# Tarjeta_Prototipo_L6470.net
KiCad netlist of a schematic drawn in EAGLE
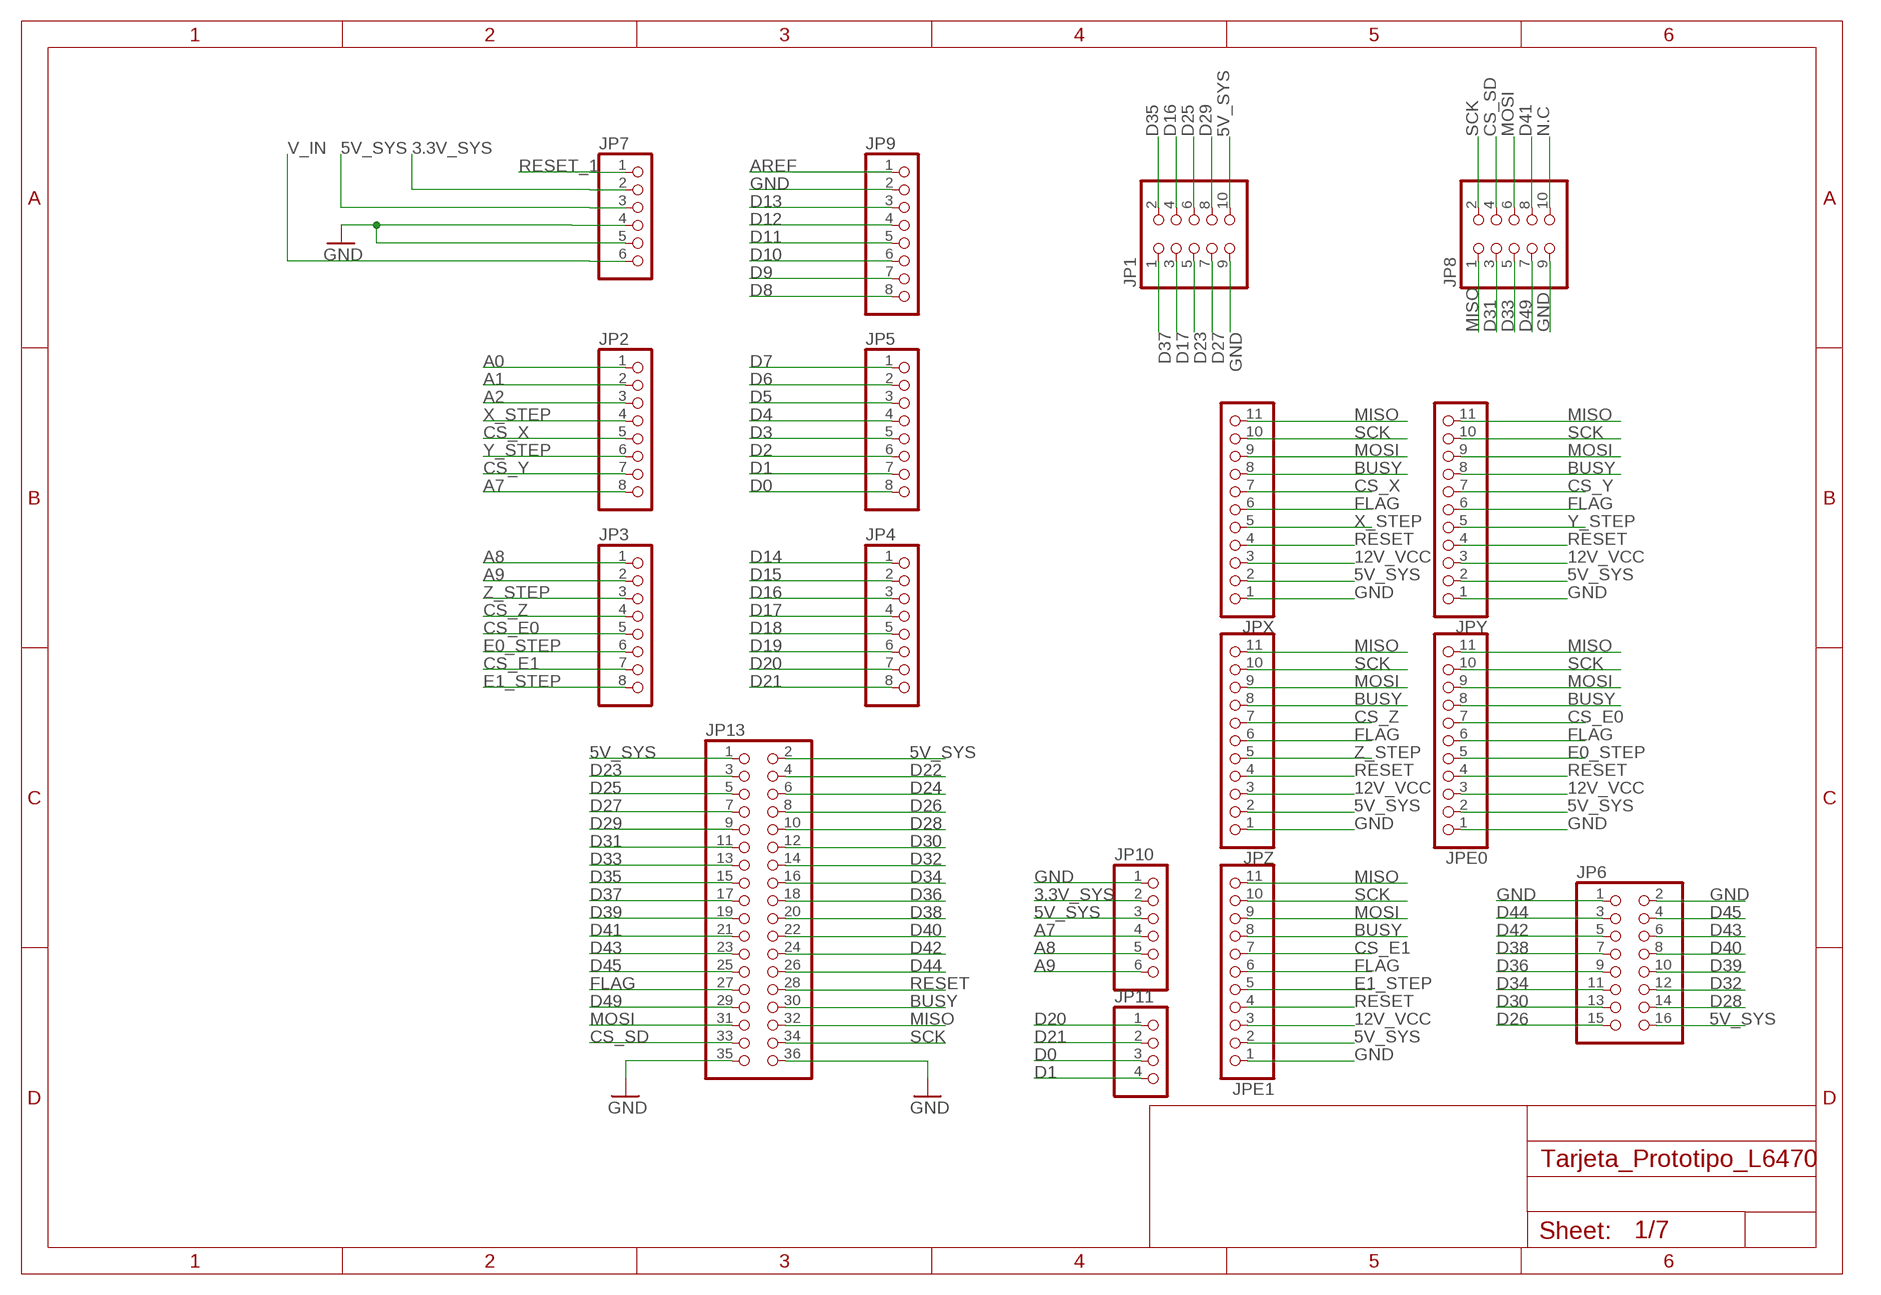
[diagram p0: schematic, sheet 1]
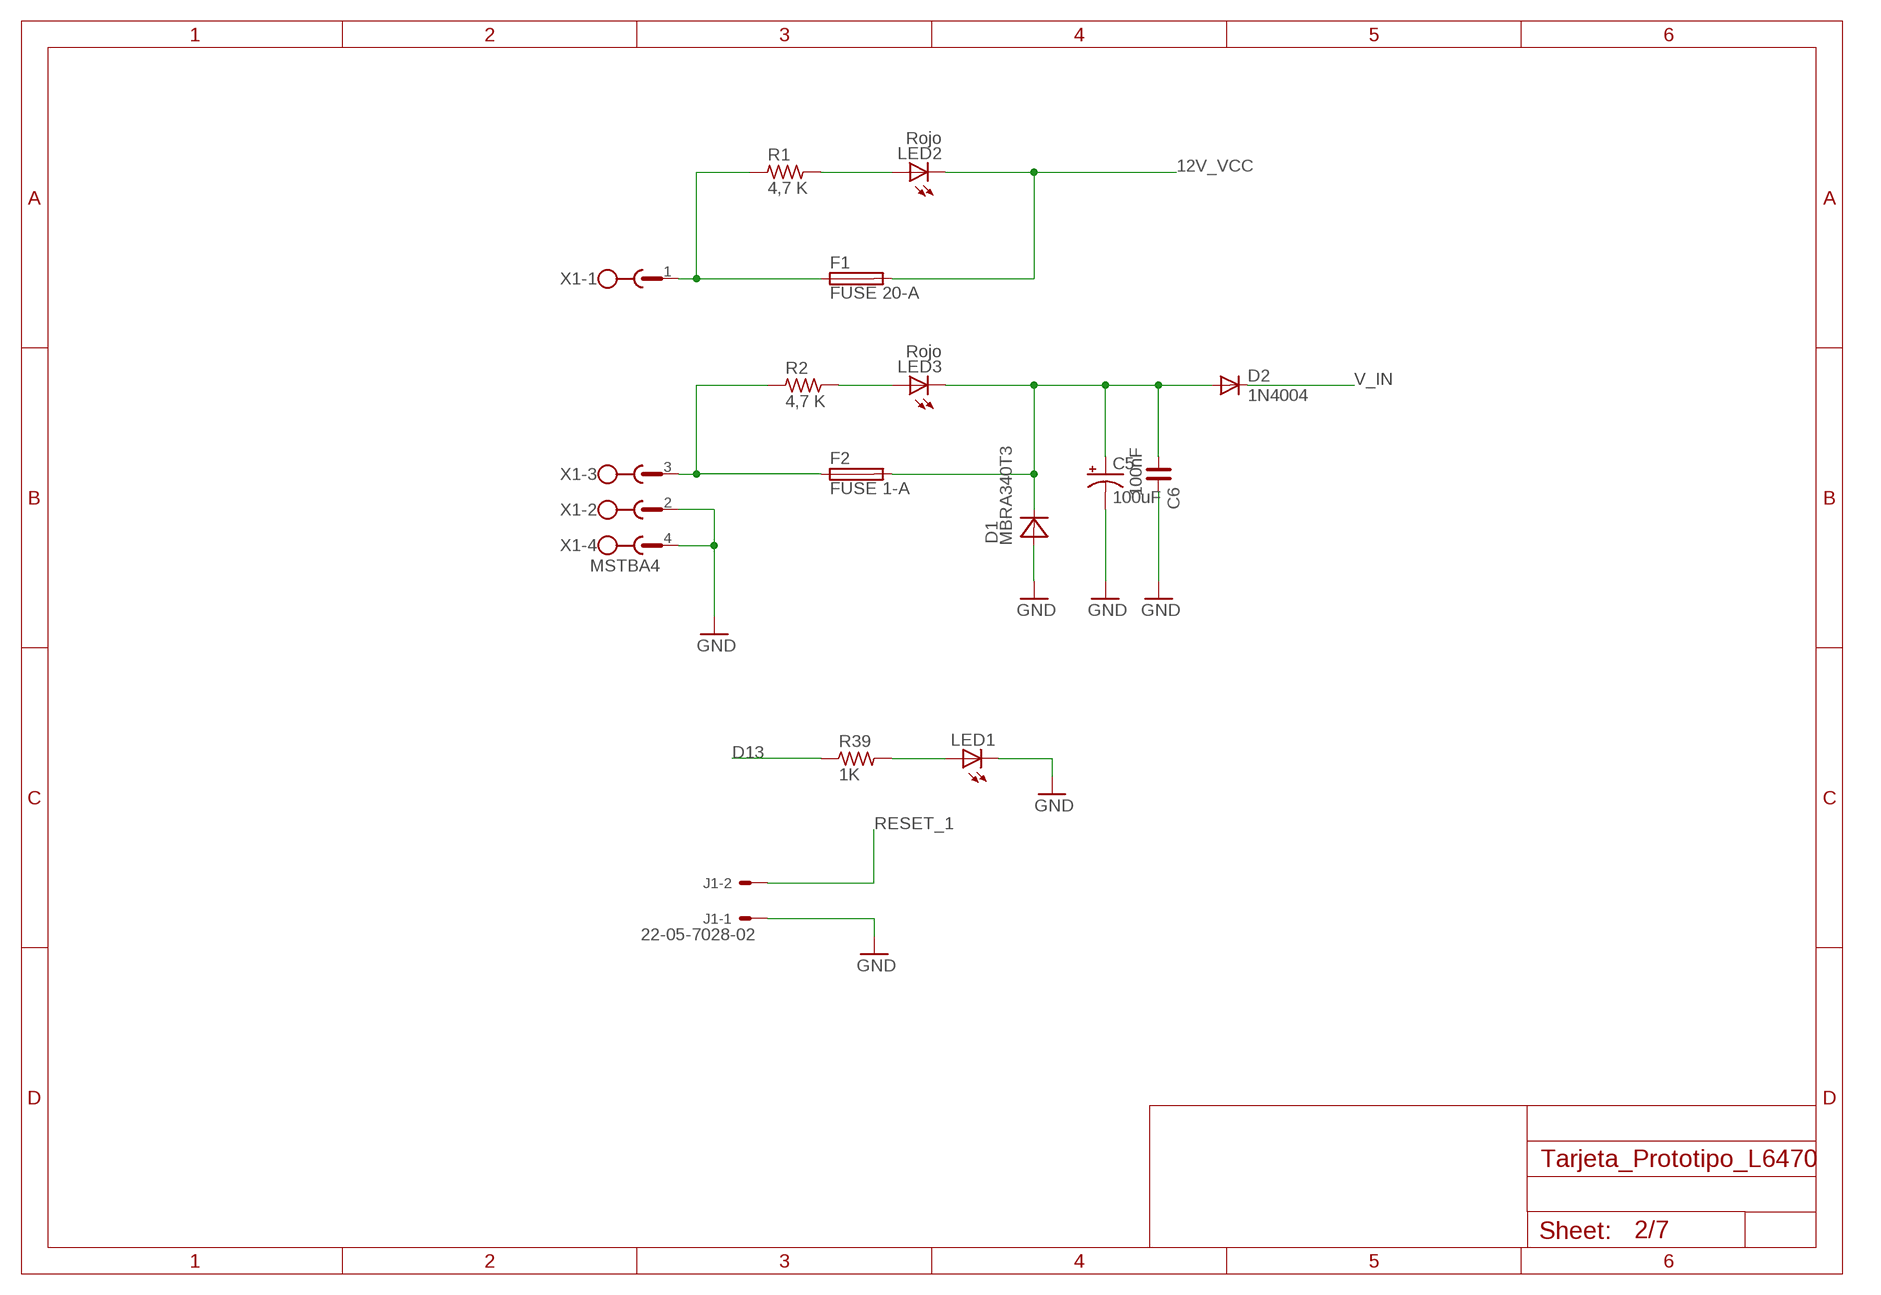
[diagram p1: schematic, sheet 2]
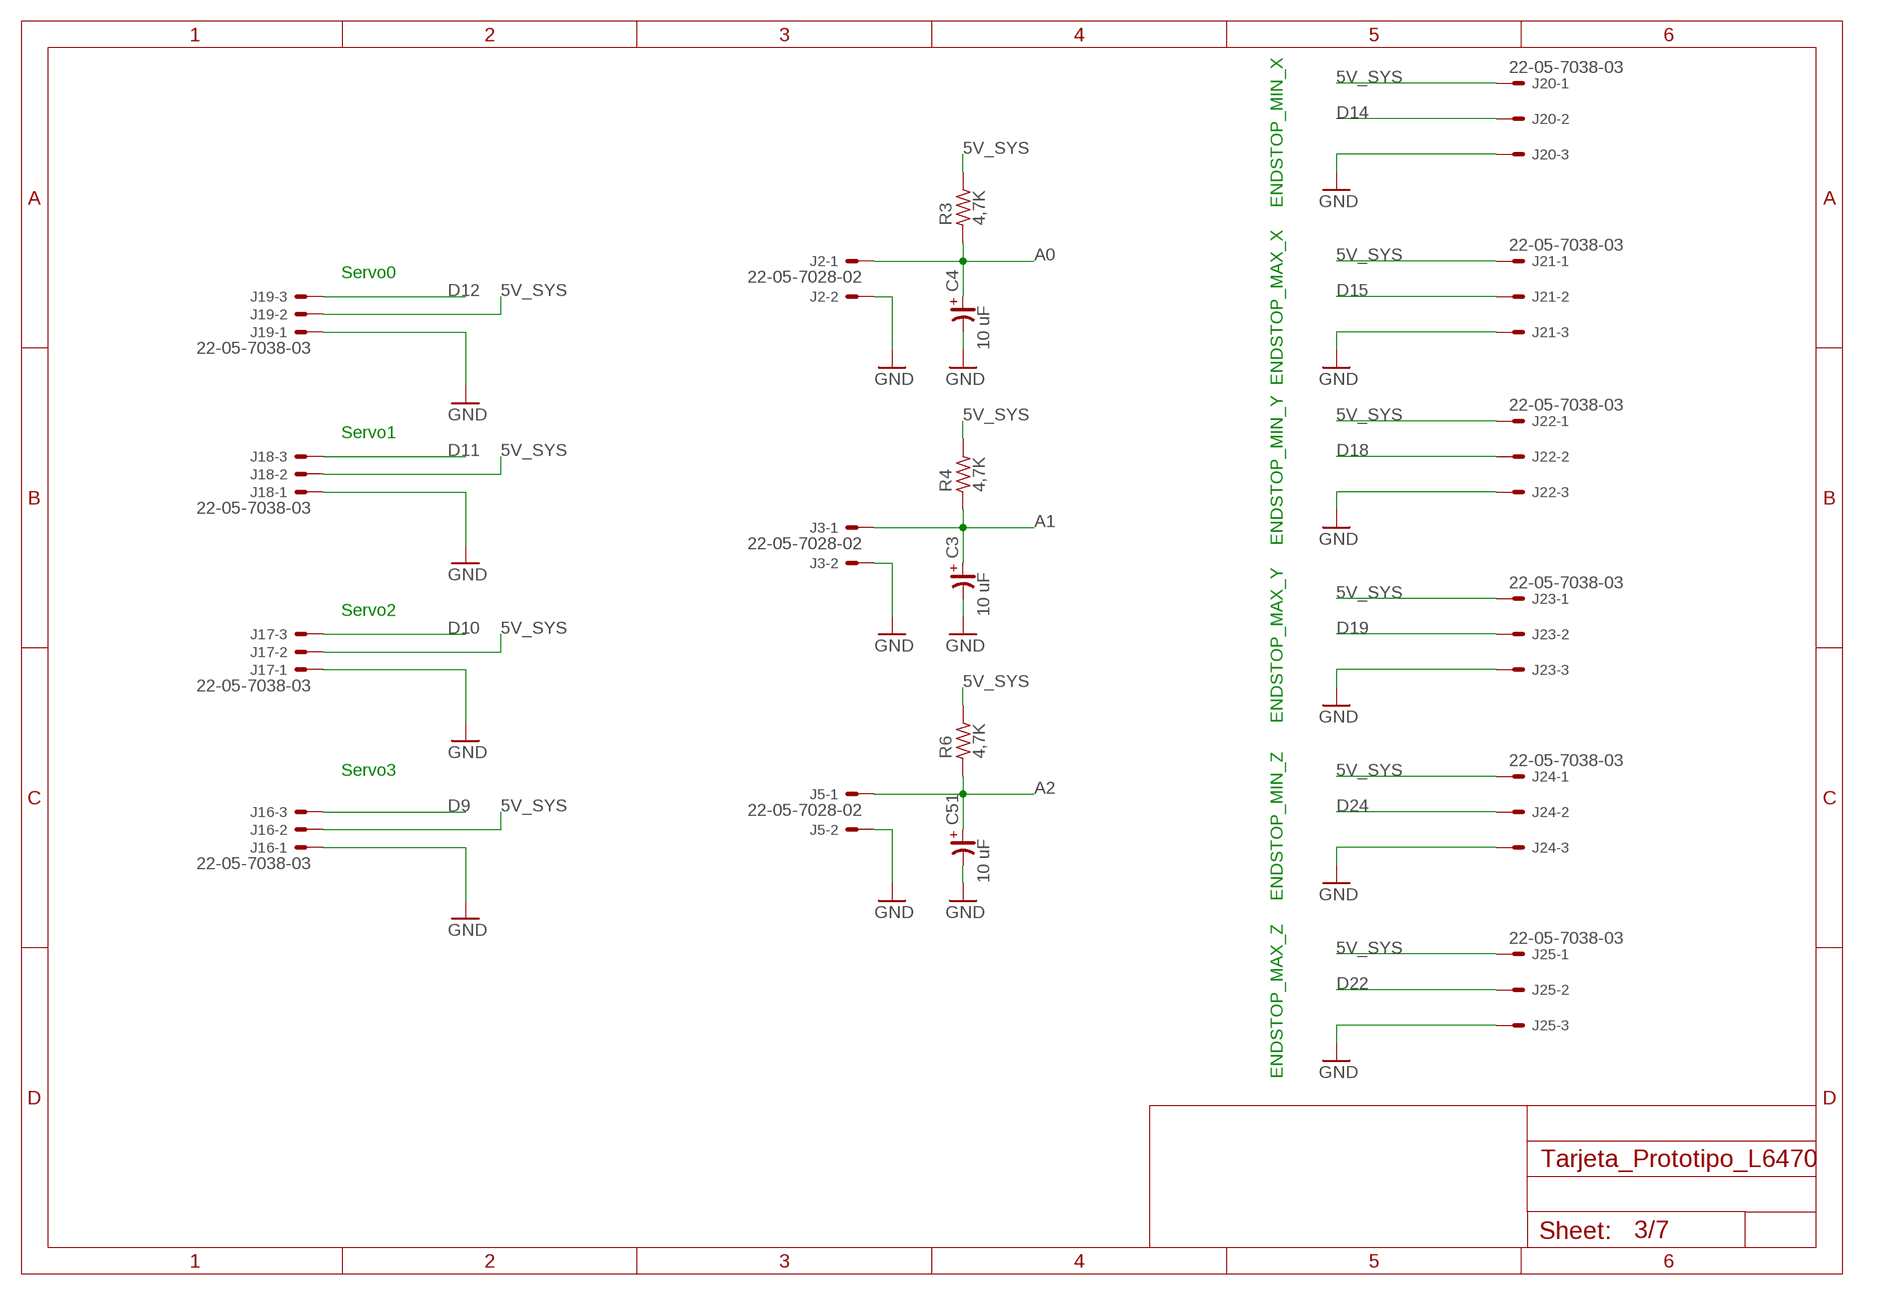
[diagram p2: schematic, sheet 3]
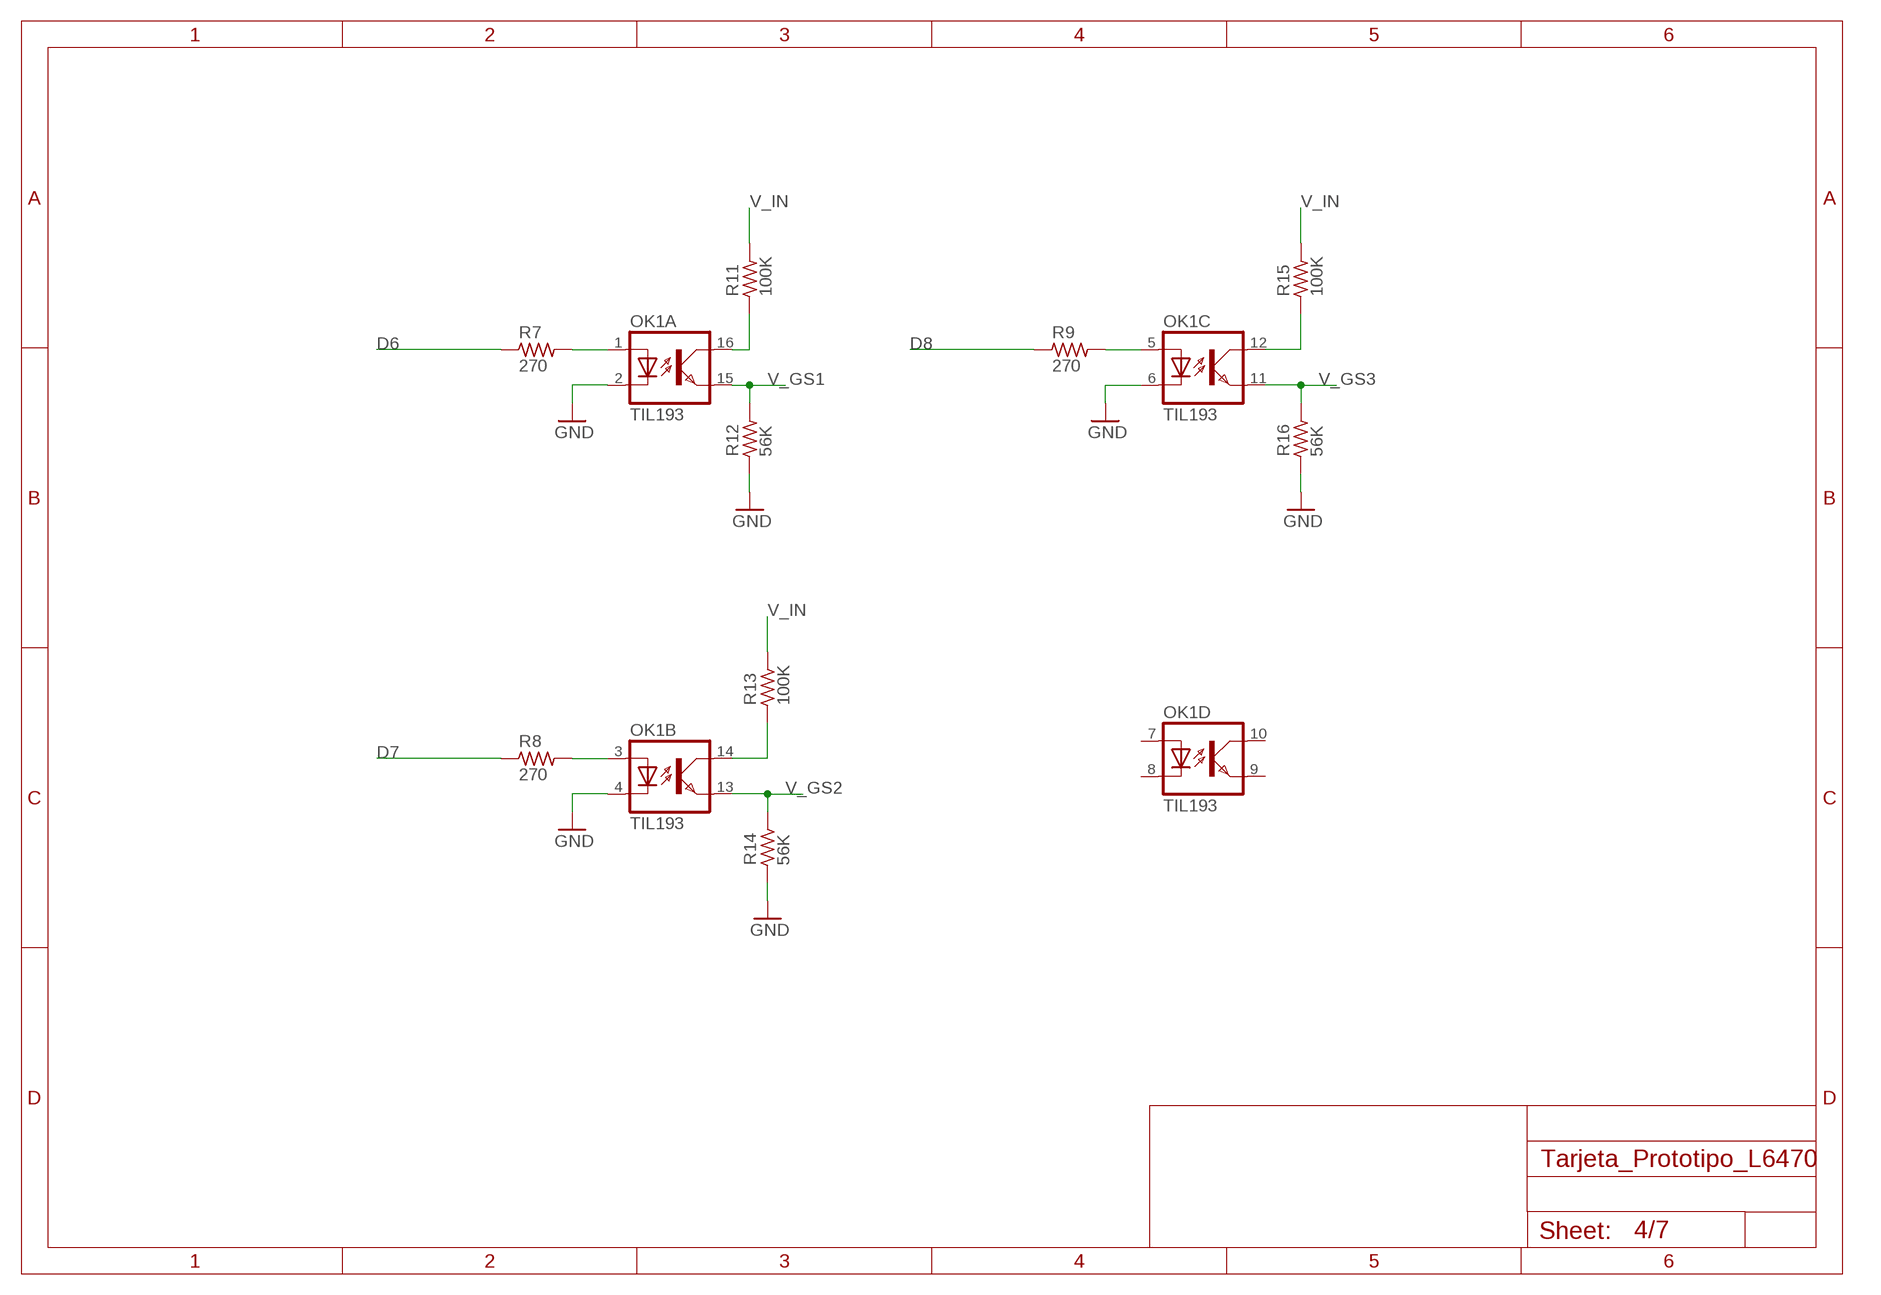
[diagram p3: schematic, sheet 4]
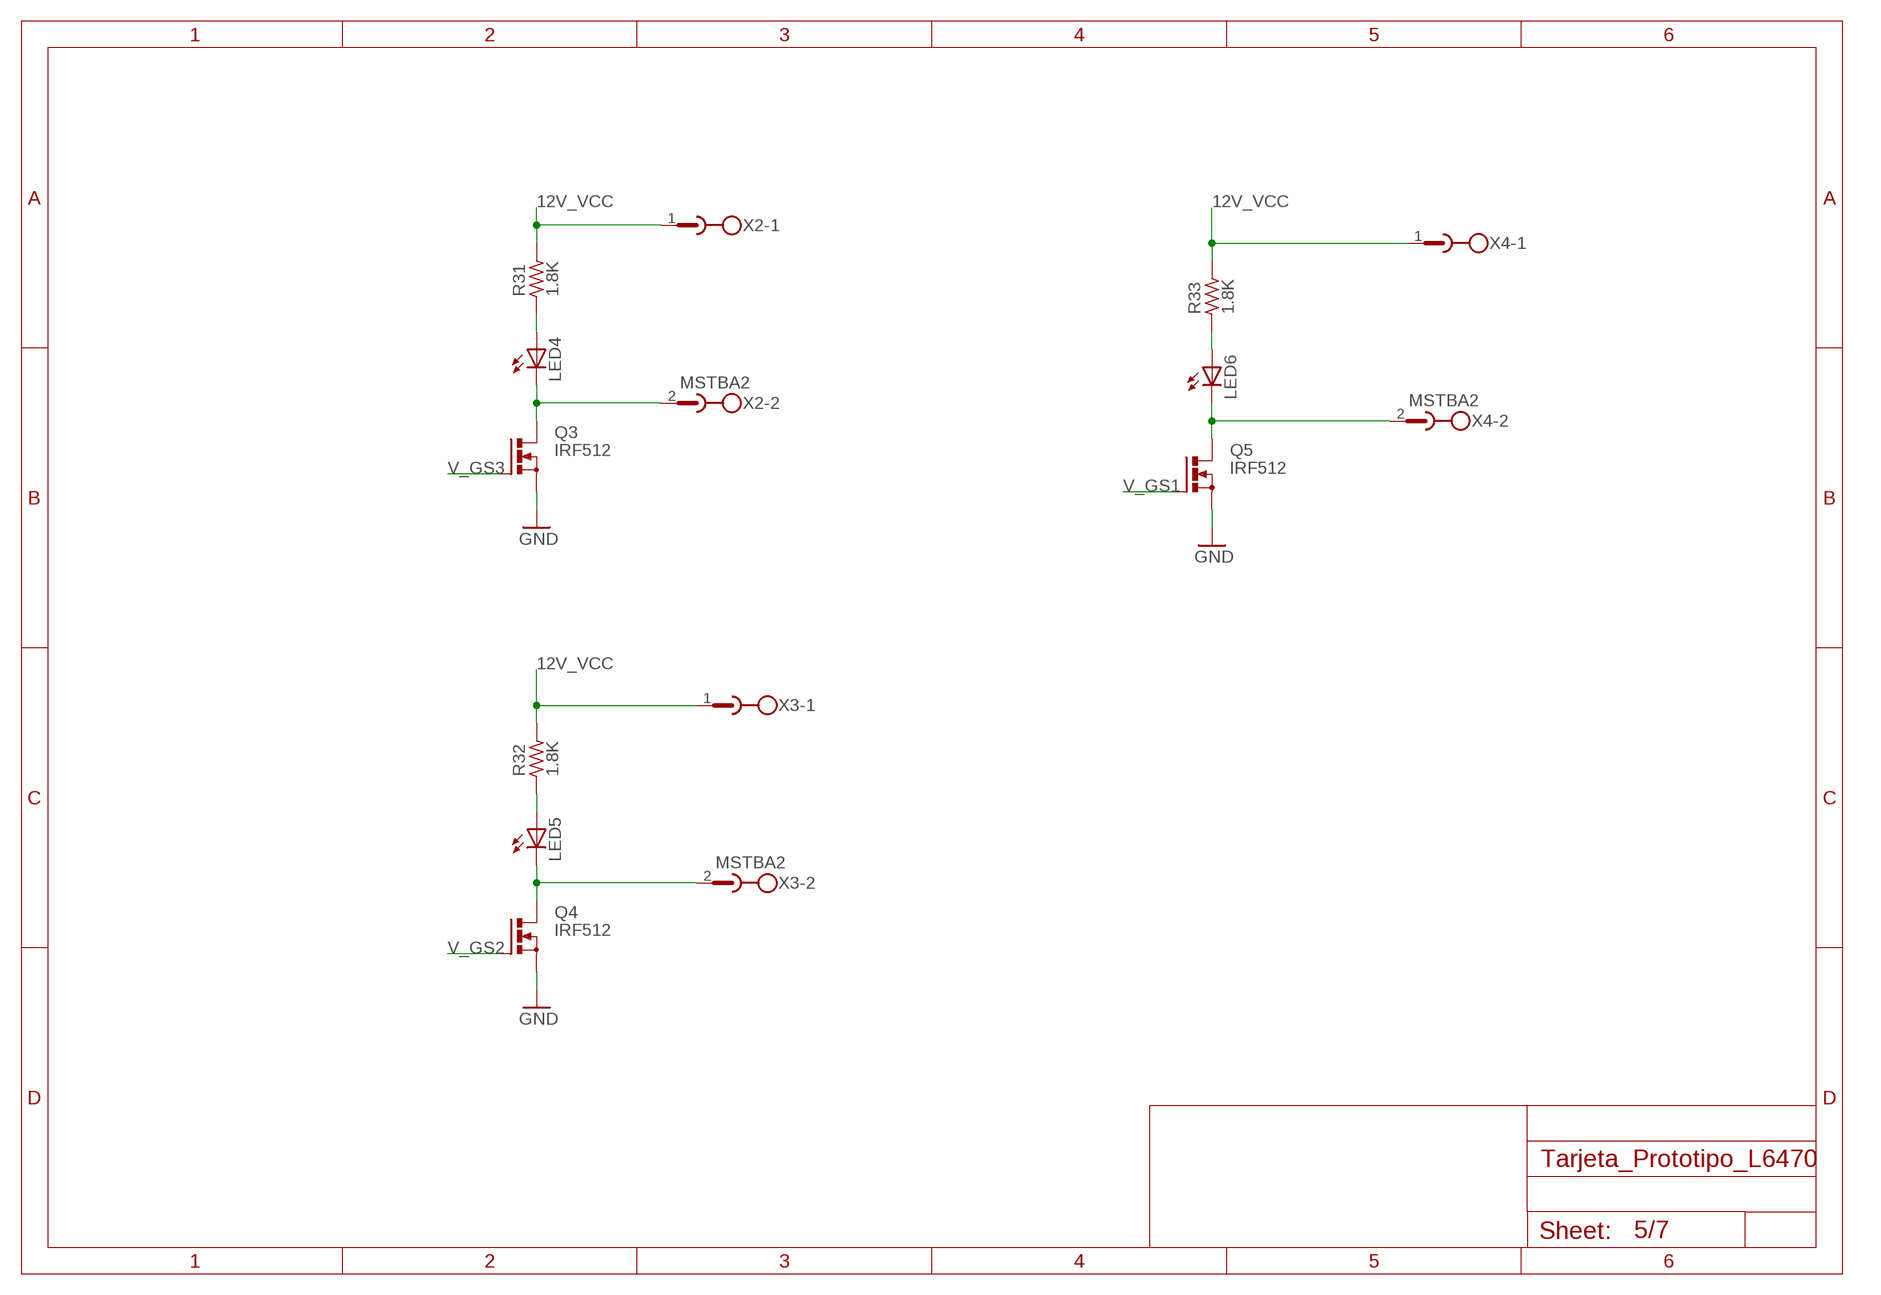
[diagram p4: schematic, sheet 5]
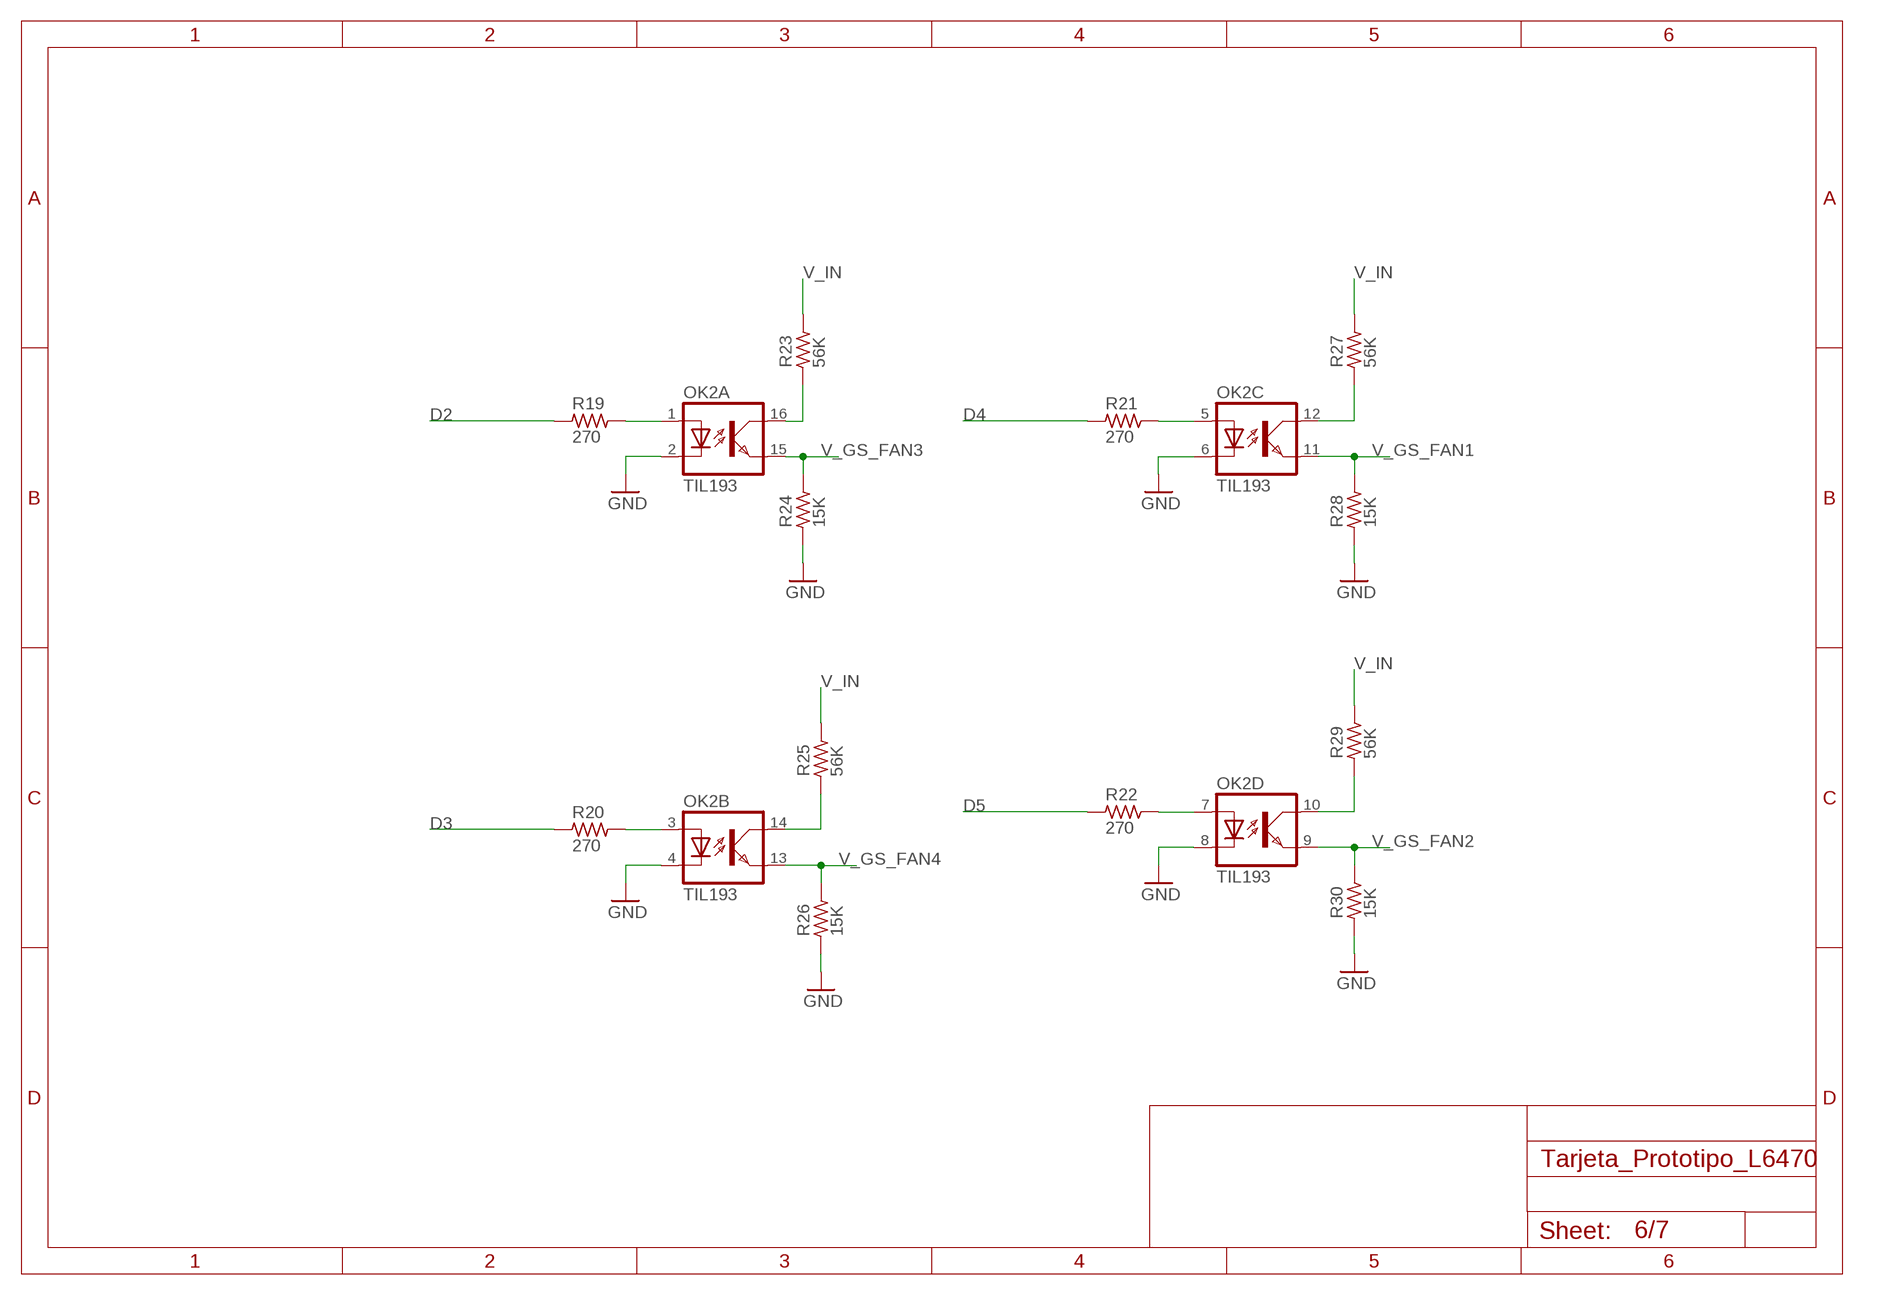
[diagram p5: schematic, sheet 6]
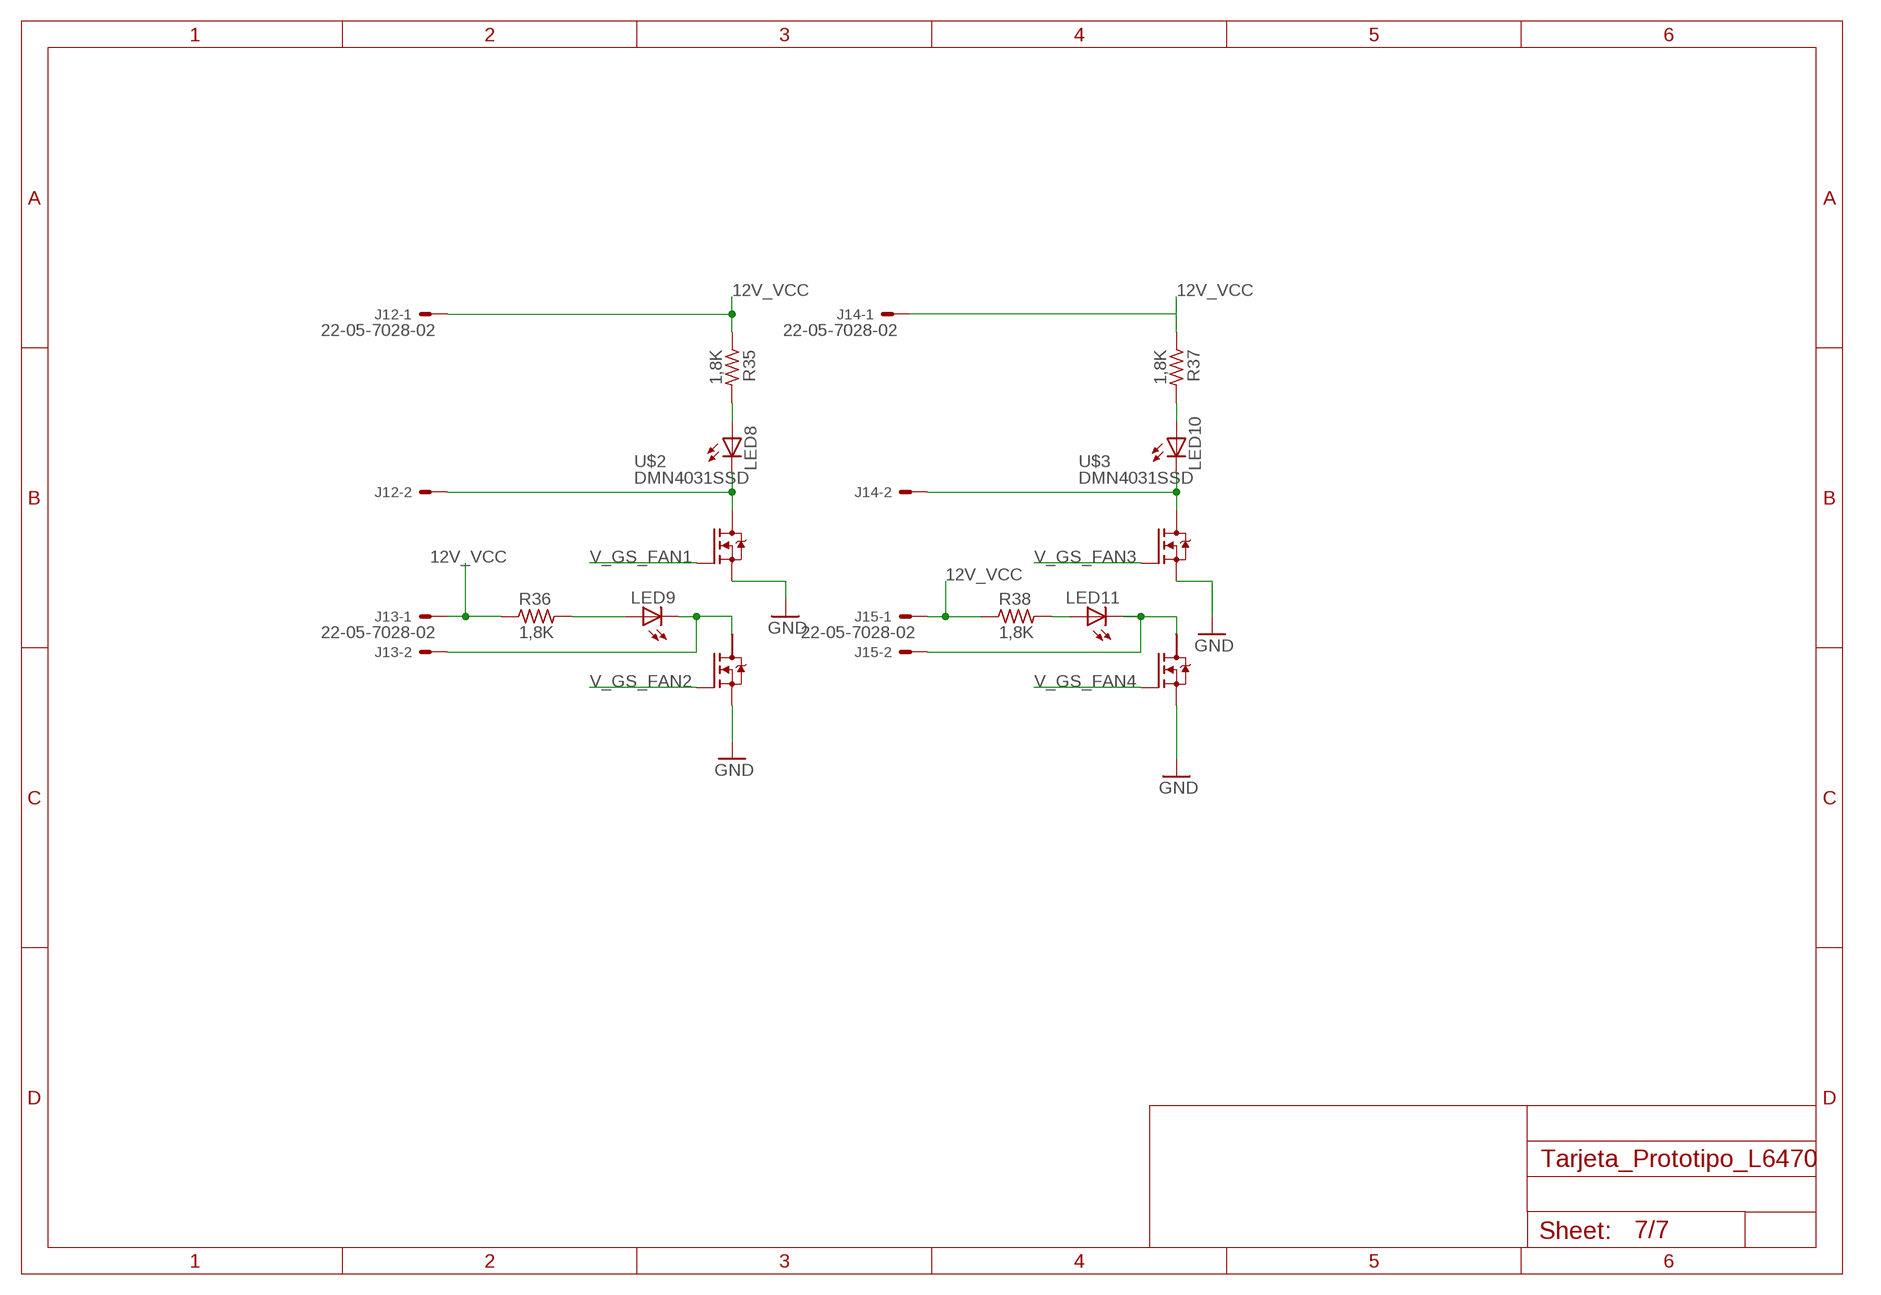
[diagram p6: schematic, sheet 7]

(export (version "E")
  (design (tool "Eeschema 10.0.6"))
  (components
    (comp (ref "OK1")
      (value "TIL193")
      (footprint "eagle-import:DIL16")
      (libsource (lib "eagle-import") (part "TIL193"))
    )
    (comp (ref "R7")
      (value "270")
      (footprint "eagle-import:R1206")
      (libsource (lib "eagle-import") (part "R_1206"))
    )
    (comp (ref "R8")
      (value "270")
      (footprint "eagle-import:R1206")
      (libsource (lib "eagle-import") (part "R_1206"))
    )
    (comp (ref "R9")
      (value "270")
      (footprint "eagle-import:R1206")
      (libsource (lib "eagle-import") (part "R_1206"))
    )
    (comp (ref "R11")
      (value "100K")
      (footprint "eagle-import:R1206")
      (libsource (lib "eagle-import") (part "R_1206"))
    )
    (comp (ref "R12")
      (value "56K")
      (footprint "eagle-import:R1206")
      (libsource (lib "eagle-import") (part "R_1206"))
    )
    (comp (ref "R13")
      (value "100K")
      (footprint "eagle-import:R1206")
      (libsource (lib "eagle-import") (part "R_1206"))
    )
    (comp (ref "R14")
      (value "56K")
      (footprint "eagle-import:R1206")
      (libsource (lib "eagle-import") (part "R_1206"))
    )
    (comp (ref "R15")
      (value "100K")
      (footprint "eagle-import:R1206")
      (libsource (lib "eagle-import") (part "R_1206"))
    )
    (comp (ref "R16")
      (value "56K")
      (footprint "eagle-import:R1206")
      (libsource (lib "eagle-import") (part "R_1206"))
    )
    (comp (ref "C3")
      (value "10 uF")
      (footprint "eagle-import:CSV-B")
      (libsource (lib "eagle-import") (part "CP_SV-B"))
    )
    (comp (ref "C4")
      (value "10 uF")
      (footprint "eagle-import:CSV-B")
      (libsource (lib "eagle-import") (part "CP_SV-B"))
    )
    (comp (ref "C51")
      (value "10 uF")
      (footprint "eagle-import:CSV-B")
      (libsource (lib "eagle-import") (part "CP_SV-B"))
    )
    (comp (ref "J2")
      (value "22-05-7028-02")
      (footprint "eagle-import:7395-02")
      (libsource (lib "eagle-import") (part "22-?-0205-7028"))
    )
    (comp (ref "J3")
      (value "22-05-7028-02")
      (footprint "eagle-import:7395-02")
      (libsource (lib "eagle-import") (part "22-?-0205-7028"))
    )
    (comp (ref "J5")
      (value "22-05-7028-02")
      (footprint "eagle-import:7395-02")
      (libsource (lib "eagle-import") (part "22-?-0205-7028"))
    )
    (comp (ref "J16")
      (value "22-05-7038-03")
      (footprint "eagle-import:7395-03")
      (libsource (lib "eagle-import") (part "22-?-0305-7038"))
    )
    (comp (ref "J17")
      (value "22-05-7038-03")
      (footprint "eagle-import:7395-03")
      (libsource (lib "eagle-import") (part "22-?-0305-7038"))
    )
    (comp (ref "J18")
      (value "22-05-7038-03")
      (footprint "eagle-import:7395-03")
      (libsource (lib "eagle-import") (part "22-?-0305-7038"))
    )
    (comp (ref "J19")
      (value "22-05-7038-03")
      (footprint "eagle-import:7395-03")
      (libsource (lib "eagle-import") (part "22-?-0305-7038"))
    )
    (comp (ref "J20")
      (value "22-05-7038-03")
      (footprint "eagle-import:7395-03")
      (libsource (lib "eagle-import") (part "22-?-0305-7038"))
    )
    (comp (ref "J21")
      (value "22-05-7038-03")
      (footprint "eagle-import:7395-03")
      (libsource (lib "eagle-import") (part "22-?-0305-7038"))
    )
    (comp (ref "J22")
      (value "22-05-7038-03")
      (footprint "eagle-import:7395-03")
      (libsource (lib "eagle-import") (part "22-?-0305-7038"))
    )
    (comp (ref "J23")
      (value "22-05-7038-03")
      (footprint "eagle-import:7395-03")
      (libsource (lib "eagle-import") (part "22-?-0305-7038"))
    )
    (comp (ref "J24")
      (value "22-05-7038-03")
      (footprint "eagle-import:7395-03")
      (libsource (lib "eagle-import") (part "22-?-0305-7038"))
    )
    (comp (ref "J25")
      (value "22-05-7038-03")
      (footprint "eagle-import:7395-03")
      (libsource (lib "eagle-import") (part "22-?-0305-7038"))
    )
    (comp (ref "R3")
      (value "4,7K")
      (footprint "eagle-import:R1206")
      (libsource (lib "eagle-import") (part "R_1206"))
    )
    (comp (ref "R4")
      (value "4,7K")
      (footprint "eagle-import:R1206")
      (libsource (lib "eagle-import") (part "R_1206"))
    )
    (comp (ref "R6")
      (value "4,7K")
      (footprint "eagle-import:R1206")
      (libsource (lib "eagle-import") (part "R_1206"))
    )
    (comp (ref "OK2")
      (value "TIL193")
      (footprint "eagle-import:DIL16")
      (libsource (lib "eagle-import") (part "TIL193"))
    )
    (comp (ref "R19")
      (value "270")
      (footprint "eagle-import:R1206")
      (libsource (lib "eagle-import") (part "R_1206"))
    )
    (comp (ref "R20")
      (value "270")
      (footprint "eagle-import:R1206")
      (libsource (lib "eagle-import") (part "R_1206"))
    )
    (comp (ref "R21")
      (value "270")
      (footprint "eagle-import:R1206")
      (libsource (lib "eagle-import") (part "R_1206"))
    )
    (comp (ref "R22")
      (value "270")
      (footprint "eagle-import:R1206")
      (libsource (lib "eagle-import") (part "R_1206"))
    )
    (comp (ref "R23")
      (value "56K")
      (footprint "eagle-import:R1206")
      (libsource (lib "eagle-import") (part "R_1206"))
    )
    (comp (ref "R24")
      (value "15K")
      (footprint "eagle-import:R1206")
      (libsource (lib "eagle-import") (part "R_1206"))
    )
    (comp (ref "R25")
      (value "56K")
      (footprint "eagle-import:R1206")
      (libsource (lib "eagle-import") (part "R_1206"))
    )
    (comp (ref "R26")
      (value "15K")
      (footprint "eagle-import:R1206")
      (libsource (lib "eagle-import") (part "R_1206"))
    )
    (comp (ref "R27")
      (value "56K")
      (footprint "eagle-import:R1206")
      (libsource (lib "eagle-import") (part "R_1206"))
    )
    (comp (ref "R28")
      (value "15K")
      (footprint "eagle-import:R1206")
      (libsource (lib "eagle-import") (part "R_1206"))
    )
    (comp (ref "R29")
      (value "56K")
      (footprint "eagle-import:R1206")
      (libsource (lib "eagle-import") (part "R_1206"))
    )
    (comp (ref "R30")
      (value "15K")
      (footprint "eagle-import:R1206")
      (libsource (lib "eagle-import") (part "R_1206"))
    )
    (comp (ref "JP1")
      (value "PINHD-2X5")
      (footprint "eagle-import:2X05")
      (libsource (lib "eagle-import") (part "PINHD-2X5"))
    )
    (comp (ref "JP2")
      (value "PINHD-1X8")
      (footprint "eagle-import:1X08")
      (libsource (lib "eagle-import") (part "PINHD-1X8"))
    )
    (comp (ref "JP3")
      (value "PINHD-1X8")
      (footprint "eagle-import:1X08")
      (libsource (lib "eagle-import") (part "PINHD-1X8"))
    )
    (comp (ref "JP4")
      (value "PINHD-1X8")
      (footprint "eagle-import:1X08")
      (libsource (lib "eagle-import") (part "PINHD-1X8"))
    )
    (comp (ref "JP5")
      (value "PINHD-1X8")
      (footprint "eagle-import:1X08")
      (libsource (lib "eagle-import") (part "PINHD-1X8"))
    )
    (comp (ref "JP6")
      (value "PINHD-2X8")
      (footprint "eagle-import:2X08")
      (libsource (lib "eagle-import") (part "PINHD-2X8"))
    )
    (comp (ref "JP7")
      (value "PINHD-1X6")
      (footprint "eagle-import:1X06")
      (libsource (lib "eagle-import") (part "PINHD-1X6"))
    )
    (comp (ref "JP8")
      (value "PINHD-2X5")
      (footprint "eagle-import:2X05")
      (libsource (lib "eagle-import") (part "PINHD-2X5"))
    )
    (comp (ref "JP9")
      (value "PINHD-1X8")
      (footprint "eagle-import:1X08")
      (libsource (lib "eagle-import") (part "PINHD-1X8"))
    )
    (comp (ref "JP10")
      (value "PINHD-1X6")
      (footprint "eagle-import:1X06")
      (libsource (lib "eagle-import") (part "PINHD-1X6"))
    )
    (comp (ref "JP11")
      (value "PINHD-1X4")
      (footprint "eagle-import:1X04")
      (libsource (lib "eagle-import") (part "PINHD-1X4"))
    )
    (comp (ref "JP13")
      (value "PINHD-2X18")
      (footprint "eagle-import:2X18")
      (libsource (lib "eagle-import") (part "PINHD-2X18"))
    )
    (comp (ref "JPE0")
      (value "PINHD-1X11")
      (footprint "eagle-import:1X11")
      (libsource (lib "eagle-import") (part "PINHD-1X11"))
    )
    (comp (ref "JPE1")
      (value "PINHD-1X11")
      (footprint "eagle-import:1X11")
      (libsource (lib "eagle-import") (part "PINHD-1X11"))
    )
    (comp (ref "JPX")
      (value "PINHD-1X11")
      (footprint "eagle-import:1X11")
      (libsource (lib "eagle-import") (part "PINHD-1X11"))
    )
    (comp (ref "JPY")
      (value "PINHD-1X11")
      (footprint "eagle-import:1X11")
      (libsource (lib "eagle-import") (part "PINHD-1X11"))
    )
    (comp (ref "JPZ")
      (value "PINHD-1X11")
      (footprint "eagle-import:1X11")
      (libsource (lib "eagle-import") (part "PINHD-1X11"))
    )
    (comp (ref "J12")
      (value "22-05-7028-02")
      (footprint "eagle-import:7395-02")
      (libsource (lib "eagle-import") (part "22-?-0205-7028"))
    )
    (comp (ref "J13")
      (value "22-05-7028-02")
      (footprint "eagle-import:7395-02")
      (libsource (lib "eagle-import") (part "22-?-0205-7028"))
    )
    (comp (ref "J14")
      (value "22-05-7028-02")
      (footprint "eagle-import:7395-02")
      (libsource (lib "eagle-import") (part "22-?-0205-7028"))
    )
    (comp (ref "J15")
      (value "22-05-7028-02")
      (footprint "eagle-import:7395-02")
      (libsource (lib "eagle-import") (part "22-?-0205-7028"))
    )
    (comp (ref "LED8")
      (value "LEDSMT1206")
      (footprint "eagle-import:1206")
      (libsource (lib "eagle-import") (part "LEDSMT1206"))
    )
    (comp (ref "LED9")
      (value "LEDSMT1206")
      (footprint "eagle-import:1206")
      (libsource (lib "eagle-import") (part "LEDSMT1206"))
    )
    (comp (ref "LED10")
      (value "LEDSMT1206")
      (footprint "eagle-import:1206")
      (libsource (lib "eagle-import") (part "LEDSMT1206"))
    )
    (comp (ref "LED11")
      (value "LEDSMT1206")
      (footprint "eagle-import:1206")
      (libsource (lib "eagle-import") (part "LEDSMT1206"))
    )
    (comp (ref "R35")
      (value "1,8K")
      (footprint "eagle-import:R1206")
      (libsource (lib "eagle-import") (part "R_1206"))
    )
    (comp (ref "R36")
      (value "1,8K")
      (footprint "eagle-import:R1206")
      (libsource (lib "eagle-import") (part "R_1206"))
    )
    (comp (ref "R37")
      (value "1,8K")
      (footprint "eagle-import:R1206")
      (libsource (lib "eagle-import") (part "R_1206"))
    )
    (comp (ref "R38")
      (value "1,8K")
      (footprint "eagle-import:R1206")
      (libsource (lib "eagle-import") (part "R_1206"))
    )
    (comp (ref "U$2")
      (value "DMN4031SSD")
      (footprint "eagle-import:DMN4031SSD")
      (libsource (lib "eagle-import") (part "DMN4031SSD"))
    )
    (comp (ref "U$3")
      (value "DMN4031SSD")
      (footprint "eagle-import:DMN4031SSD")
      (libsource (lib "eagle-import") (part "DMN4031SSD"))
    )
    (comp (ref "LED4")
      (value "LEDSMT1206")
      (footprint "eagle-import:1206")
      (libsource (lib "eagle-import") (part "LEDSMT1206"))
    )
    (comp (ref "LED5")
      (value "LEDSMT1206")
      (footprint "eagle-import:1206")
      (libsource (lib "eagle-import") (part "LEDSMT1206"))
    )
    (comp (ref "LED6")
      (value "LEDSMT1206")
      (footprint "eagle-import:1206")
      (libsource (lib "eagle-import") (part "LEDSMT1206"))
    )
    (comp (ref "Q3")
      (value "IRF512")
      (footprint "eagle-import:TO220BV")
      (libsource (lib "eagle-import") (part "IRF512"))
    )
    (comp (ref "Q4")
      (value "IRF512")
      (footprint "eagle-import:TO220BV")
      (libsource (lib "eagle-import") (part "IRF512"))
    )
    (comp (ref "Q5")
      (value "IRF512")
      (footprint "eagle-import:TO220BV")
      (libsource (lib "eagle-import") (part "IRF512"))
    )
    (comp (ref "R31")
      (value "1.8K")
      (footprint "eagle-import:R1206")
      (libsource (lib "eagle-import") (part "R_1206"))
    )
    (comp (ref "R32")
      (value "1.8K")
      (footprint "eagle-import:R1206")
      (libsource (lib "eagle-import") (part "R_1206"))
    )
    (comp (ref "R33")
      (value "1.8K")
      (footprint "eagle-import:R1206")
      (libsource (lib "eagle-import") (part "R_1206"))
    )
    (comp (ref "X2")
      (value "MSTBA2")
      (footprint "eagle-import:MSTBA2")
      (fields (field (name "MF") "FARNELL") (field (name "MPN") "1757242"))
      (libsource (lib "eagle-import") (part "MSTBA2"))
    )
    (comp (ref "X3")
      (value "MSTBA2")
      (footprint "eagle-import:MSTBA2")
      (fields (field (name "MF") "FARNELL") (field (name "MPN") "1757242"))
      (libsource (lib "eagle-import") (part "MSTBA2"))
    )
    (comp (ref "X4")
      (value "MSTBA2")
      (footprint "eagle-import:MSTBA2")
      (fields (field (name "MF") "FARNELL") (field (name "MPN") "1757242"))
      (libsource (lib "eagle-import") (part "MSTBA2"))
    )
    (comp (ref "C5")
      (value "100uF")
      (footprint "eagle-import:153CLV-0605")
      (libsource (lib "eagle-import") (part "CPOL-US153CLV-0605"))
    )
    (comp (ref "C6")
      (value "100nF")
      (footprint "eagle-import:C1206")
      (libsource (lib "eagle-import") (part "C_1206"))
    )
    (comp (ref "D1")
      (value "MBRA340T3")
      (footprint "eagle-import:SMA")
      (libsource (lib "eagle-import") (part "MBRA340T3"))
    )
    (comp (ref "D2")
      (value "1N4004")
      (footprint "eagle-import:DO41-10")
      (libsource (lib "eagle-import") (part "1N4004"))
    )
    (comp (ref "F1")
      (value "FUSE 20-A")
      (footprint "eagle-import:3557")
      (libsource (lib "eagle-import") (part "FUSE"))
    )
    (comp (ref "F2")
      (value "FUSE 1-A")
      (footprint "eagle-import:3557")
      (libsource (lib "eagle-import") (part "FUSE"))
    )
    (comp (ref "J1")
      (value "22-05-7028-02")
      (footprint "eagle-import:7395-02")
      (libsource (lib "eagle-import") (part "22-?-0205-7028"))
    )
    (comp (ref "LED1")
      (value "LEDSMT1206")
      (footprint "eagle-import:1206")
      (libsource (lib "eagle-import") (part "LEDSMT1206"))
    )
    (comp (ref "LED2")
      (value "Rojo")
      (footprint "eagle-import:1206")
      (libsource (lib "eagle-import") (part "LEDSMT1206"))
    )
    (comp (ref "LED3")
      (value "Rojo")
      (footprint "eagle-import:1206")
      (libsource (lib "eagle-import") (part "LEDSMT1206"))
    )
    (comp (ref "R1")
      (value "4,7 K")
      (footprint "eagle-import:R1206")
      (libsource (lib "eagle-import") (part "R_1206"))
    )
    (comp (ref "R2")
      (value "4,7 K")
      (footprint "eagle-import:R1206")
      (libsource (lib "eagle-import") (part "R_1206"))
    )
    (comp (ref "R39")
      (value "1K")
      (footprint "eagle-import:R1206")
      (libsource (lib "eagle-import") (part "R_1206"))
    )
    (comp (ref "X1")
      (value "MSTBA4")
      (footprint "eagle-import:MSTBA4")
      (fields (field (name "MF") "FARNELL") (field (name "MPN") "1757268"))
      (libsource (lib "eagle-import") (part "MSTBA4"))
    )
  )
  (nets
    (net (code "1") (name "3.3V_SYS") (class "Default")
      (node (ref "JP10") (pin "2") (pinfunction "2_2") (pintype "passive"))
      (node (ref "JP7") (pin "2") (pinfunction "2_2") (pintype "passive"))
    )
    (net (code "2") (name "5V_SYS") (class "Default")
      (node (ref "J16") (pin "2") (pinfunction "S_2") (pintype "passive"))
      (node (ref "J17") (pin "2") (pinfunction "S_2") (pintype "passive"))
      (node (ref "J18") (pin "2") (pinfunction "S_2") (pintype "passive"))
      (node (ref "J19") (pin "2") (pinfunction "S_2") (pintype "passive"))
      (node (ref "J20") (pin "1") (pinfunction "S_1") (pintype "passive"))
      (node (ref "J21") (pin "1") (pinfunction "S_1") (pintype "passive"))
      (node (ref "J22") (pin "1") (pinfunction "S_1") (pintype "passive"))
      (node (ref "J23") (pin "1") (pinfunction "S_1") (pintype "passive"))
      (node (ref "J24") (pin "1") (pinfunction "S_1") (pintype "passive"))
      (node (ref "J25") (pin "1") (pinfunction "S_1") (pintype "passive"))
      (node (ref "JP1") (pin "10") (pinfunction "10_10") (pintype "passive"))
      (node (ref "JP10") (pin "3") (pinfunction "3_3") (pintype "passive"))
      (node (ref "JP13") (pin "1") (pinfunction "1_1") (pintype "passive"))
      (node (ref "JP13") (pin "2") (pinfunction "2_2") (pintype "passive"))
      (node (ref "JP6") (pin "16") (pinfunction "16_16") (pintype "passive"))
      (node (ref "JP7") (pin "3") (pinfunction "3_3") (pintype "passive"))
      (node (ref "JPE0") (pin "2") (pinfunction "2_2") (pintype "passive"))
      (node (ref "JPE1") (pin "2") (pinfunction "2_2") (pintype "passive"))
      (node (ref "JPX") (pin "2") (pinfunction "2_2") (pintype "passive"))
      (node (ref "JPY") (pin "2") (pinfunction "2_2") (pintype "passive"))
      (node (ref "JPZ") (pin "2") (pinfunction "2_2") (pintype "passive"))
      (node (ref "R3") (pin "2") (pinfunction "2_2") (pintype "passive"))
      (node (ref "R4") (pin "2") (pinfunction "2_2") (pintype "passive"))
      (node (ref "R6") (pin "2") (pinfunction "2_2") (pintype "passive"))
    )
    (net (code "3") (name "12V_VCC") (class "Default")
      (node (ref "F1") (pin "P$3") (pinfunction "2_P$3") (pintype "passive"))
      (node (ref "F1") (pin "P$4") (pinfunction "2_P$4") (pintype "passive"))
      (node (ref "J12") (pin "1") (pinfunction "S_1") (pintype "passive"))
      (node (ref "J13") (pin "1") (pinfunction "S_1") (pintype "passive"))
      (node (ref "J14") (pin "1") (pinfunction "S_1") (pintype "passive"))
      (node (ref "J15") (pin "1") (pinfunction "S_1") (pintype "passive"))
      (node (ref "JPE0") (pin "3") (pinfunction "3_3") (pintype "passive"))
      (node (ref "JPE1") (pin "3") (pinfunction "3_3") (pintype "passive"))
      (node (ref "JPX") (pin "3") (pinfunction "3_3") (pintype "passive"))
      (node (ref "JPY") (pin "3") (pinfunction "3_3") (pintype "passive"))
      (node (ref "JPZ") (pin "3") (pinfunction "3_3") (pintype "passive"))
      (node (ref "LED2") (pin "C") (pinfunction "C_C") (pintype "passive"))
      (node (ref "R31") (pin "2") (pinfunction "2_2") (pintype "passive"))
      (node (ref "R32") (pin "2") (pinfunction "2_2") (pintype "passive"))
      (node (ref "R33") (pin "2") (pinfunction "2_2") (pintype "passive"))
      (node (ref "R35") (pin "1") (pinfunction "1_1") (pintype "passive"))
      (node (ref "R36") (pin "1") (pinfunction "1_1") (pintype "passive"))
      (node (ref "R37") (pin "1") (pinfunction "1_1") (pintype "passive"))
      (node (ref "R38") (pin "1") (pinfunction "1_1") (pintype "passive"))
      (node (ref "X2") (pin "1") (pinfunction "1_1") (pintype "passive"))
      (node (ref "X3") (pin "1") (pinfunction "1_1") (pintype "passive"))
      (node (ref "X4") (pin "1") (pinfunction "1_1") (pintype "passive"))
    )
    (net (code "4") (name "A0") (class "Default")
      (node (ref "C4") (pin "+") (pinfunction "+_+") (pintype "passive"))
      (node (ref "J2") (pin "1") (pinfunction "S_1") (pintype "passive"))
      (node (ref "JP2") (pin "1") (pinfunction "1_1") (pintype "passive"))
      (node (ref "R3") (pin "1") (pinfunction "1_1") (pintype "passive"))
    )
    (net (code "5") (name "A1") (class "Default")
      (node (ref "C3") (pin "+") (pinfunction "+_+") (pintype "passive"))
      (node (ref "J3") (pin "1") (pinfunction "S_1") (pintype "passive"))
      (node (ref "JP2") (pin "2") (pinfunction "2_2") (pintype "passive"))
      (node (ref "R4") (pin "1") (pinfunction "1_1") (pintype "passive"))
    )
    (net (code "6") (name "A2") (class "Default")
      (node (ref "C51") (pin "+") (pinfunction "+_+") (pintype "passive"))
      (node (ref "J5") (pin "1") (pinfunction "S_1") (pintype "passive"))
      (node (ref "JP2") (pin "3") (pinfunction "3_3") (pintype "passive"))
      (node (ref "R6") (pin "1") (pinfunction "1_1") (pintype "passive"))
    )
    (net (code "7") (name "A7") (class "Default")
      (node (ref "JP10") (pin "4") (pinfunction "4_4") (pintype "passive"))
      (node (ref "JP2") (pin "8") (pinfunction "8_8") (pintype "passive"))
    )
    (net (code "8") (name "A8") (class "Default")
      (node (ref "JP10") (pin "5") (pinfunction "5_5") (pintype "passive"))
      (node (ref "JP3") (pin "1") (pinfunction "1_1") (pintype "passive"))
    )
    (net (code "9") (name "A9") (class "Default")
      (node (ref "JP10") (pin "6") (pinfunction "6_6") (pintype "passive"))
      (node (ref "JP3") (pin "2") (pinfunction "2_2") (pintype "passive"))
    )
    (net (code "10") (name "AREF") (class "Default")
      (node (ref "JP9") (pin "1") (pinfunction "1_1") (pintype "passive"))
    )
    (net (code "11") (name "BUSY") (class "Default")
      (node (ref "JP13") (pin "30") (pinfunction "30_30") (pintype "passive"))
      (node (ref "JPE0") (pin "8") (pinfunction "8_8") (pintype "passive"))
      (node (ref "JPE1") (pin "8") (pinfunction "8_8") (pintype "passive"))
      (node (ref "JPX") (pin "8") (pinfunction "8_8") (pintype "passive"))
      (node (ref "JPY") (pin "8") (pinfunction "8_8") (pintype "passive"))
      (node (ref "JPZ") (pin "8") (pinfunction "8_8") (pintype "passive"))
    )
    (net (code "12") (name "CS_E0") (class "Default")
      (node (ref "JP3") (pin "5") (pinfunction "5_5") (pintype "passive"))
      (node (ref "JPE0") (pin "7") (pinfunction "7_7") (pintype "passive"))
    )
    (net (code "13") (name "CS_E1") (class "Default")
      (node (ref "JP3") (pin "7") (pinfunction "7_7") (pintype "passive"))
      (node (ref "JPE1") (pin "7") (pinfunction "7_7") (pintype "passive"))
    )
    (net (code "14") (name "CS_SD") (class "Default")
      (node (ref "JP13") (pin "33") (pinfunction "33_33") (pintype "passive"))
      (node (ref "JP8") (pin "4") (pinfunction "4_4") (pintype "passive"))
    )
    (net (code "15") (name "CS_X") (class "Default")
      (node (ref "JP2") (pin "5") (pinfunction "5_5") (pintype "passive"))
      (node (ref "JPX") (pin "7") (pinfunction "7_7") (pintype "passive"))
    )
    (net (code "16") (name "CS_Y") (class "Default")
      (node (ref "JP2") (pin "7") (pinfunction "7_7") (pintype "passive"))
      (node (ref "JPY") (pin "7") (pinfunction "7_7") (pintype "passive"))
    )
    (net (code "17") (name "CS_Z") (class "Default")
      (node (ref "JP3") (pin "4") (pinfunction "4_4") (pintype "passive"))
      (node (ref "JPZ") (pin "7") (pinfunction "7_7") (pintype "passive"))
    )
    (net (code "18") (name "D0") (class "Default")
      (node (ref "JP11") (pin "3") (pinfunction "3_3") (pintype "passive"))
      (node (ref "JP5") (pin "8") (pinfunction "8_8") (pintype "passive"))
    )
    (net (code "19") (name "D1") (class "Default")
      (node (ref "JP11") (pin "4") (pinfunction "4_4") (pintype "passive"))
      (node (ref "JP5") (pin "7") (pinfunction "7_7") (pintype "passive"))
    )
    (net (code "20") (name "D2") (class "Default")
      (node (ref "JP5") (pin "6") (pinfunction "6_6") (pintype "passive"))
      (node (ref "R19") (pin "1") (pinfunction "1_1") (pintype "passive"))
    )
    (net (code "21") (name "D3") (class "Default")
      (node (ref "JP5") (pin "5") (pinfunction "5_5") (pintype "passive"))
      (node (ref "R20") (pin "1") (pinfunction "1_1") (pintype "passive"))
    )
    (net (code "22") (name "D4") (class "Default")
      (node (ref "JP5") (pin "4") (pinfunction "4_4") (pintype "passive"))
      (node (ref "R21") (pin "1") (pinfunction "1_1") (pintype "passive"))
    )
    (net (code "23") (name "D5") (class "Default")
      (node (ref "JP5") (pin "3") (pinfunction "3_3") (pintype "passive"))
      (node (ref "R22") (pin "1") (pinfunction "1_1") (pintype "passive"))
    )
    (net (code "24") (name "D6") (class "Default")
      (node (ref "JP5") (pin "2") (pinfunction "2_2") (pintype "passive"))
      (node (ref "R7") (pin "1") (pinfunction "1_1") (pintype "passive"))
    )
    (net (code "25") (name "D7") (class "Default")
      (node (ref "JP5") (pin "1") (pinfunction "1_1") (pintype "passive"))
      (node (ref "R8") (pin "1") (pinfunction "1_1") (pintype "passive"))
    )
    (net (code "26") (name "D8") (class "Default")
      (node (ref "JP9") (pin "8") (pinfunction "8_8") (pintype "passive"))
      (node (ref "R9") (pin "1") (pinfunction "1_1") (pintype "passive"))
    )
    (net (code "27") (name "D9") (class "Default")
      (node (ref "J16") (pin "3") (pinfunction "S_3") (pintype "passive"))
      (node (ref "JP9") (pin "7") (pinfunction "7_7") (pintype "passive"))
    )
    (net (code "28") (name "D10") (class "Default")
      (node (ref "J17") (pin "3") (pinfunction "S_3") (pintype "passive"))
      (node (ref "JP9") (pin "6") (pinfunction "6_6") (pintype "passive"))
    )
    (net (code "29") (name "D11") (class "Default")
      (node (ref "J18") (pin "3") (pinfunction "S_3") (pintype "passive"))
      (node (ref "JP9") (pin "5") (pinfunction "5_5") (pintype "passive"))
    )
    (net (code "30") (name "D12") (class "Default")
      (node (ref "J19") (pin "3") (pinfunction "S_3") (pintype "passive"))
      (node (ref "JP9") (pin "4") (pinfunction "4_4") (pintype "passive"))
    )
    (net (code "31") (name "D13") (class "Default")
      (node (ref "JP9") (pin "3") (pinfunction "3_3") (pintype "passive"))
      (node (ref "R39") (pin "1") (pinfunction "1_1") (pintype "passive"))
    )
    (net (code "32") (name "D14") (class "Default")
      (node (ref "J20") (pin "2") (pinfunction "S_2") (pintype "passive"))
      (node (ref "JP4") (pin "1") (pinfunction "1_1") (pintype "passive"))
    )
    (net (code "33") (name "D15") (class "Default")
      (node (ref "J21") (pin "2") (pinfunction "S_2") (pintype "passive"))
      (node (ref "JP4") (pin "2") (pinfunction "2_2") (pintype "passive"))
    )
    (net (code "34") (name "D16") (class "Default")
      (node (ref "JP1") (pin "4") (pinfunction "4_4") (pintype "passive"))
      (node (ref "JP4") (pin "3") (pinfunction "3_3") (pintype "passive"))
    )
    (net (code "35") (name "D17") (class "Default")
      (node (ref "JP1") (pin "3") (pinfunction "3_3") (pintype "passive"))
      (node (ref "JP4") (pin "4") (pinfunction "4_4") (pintype "passive"))
    )
    (net (code "36") (name "D18") (class "Default")
      (node (ref "J22") (pin "2") (pinfunction "S_2") (pintype "passive"))
      (node (ref "JP4") (pin "5") (pinfunction "5_5") (pintype "passive"))
    )
    (net (code "37") (name "D19") (class "Default")
      (node (ref "J23") (pin "2") (pinfunction "S_2") (pintype "passive"))
      (node (ref "JP4") (pin "6") (pinfunction "6_6") (pintype "passive"))
    )
    (net (code "38") (name "D20") (class "Default")
      (node (ref "JP11") (pin "1") (pinfunction "1_1") (pintype "passive"))
      (node (ref "JP4") (pin "7") (pinfunction "7_7") (pintype "passive"))
    )
    (net (code "39") (name "D21") (class "Default")
      (node (ref "JP11") (pin "2") (pinfunction "2_2") (pintype "passive"))
      (node (ref "JP4") (pin "8") (pinfunction "8_8") (pintype "passive"))
    )
    (net (code "40") (name "D22") (class "Default")
      (node (ref "J25") (pin "2") (pinfunction "S_2") (pintype "passive"))
      (node (ref "JP13") (pin "4") (pinfunction "4_4") (pintype "passive"))
    )
    (net (code "41") (name "D23") (class "Default")
      (node (ref "JP1") (pin "5") (pinfunction "5_5") (pintype "passive"))
      (node (ref "JP13") (pin "3") (pinfunction "3_3") (pintype "passive"))
    )
    (net (code "42") (name "D24") (class "Default")
      (node (ref "J24") (pin "2") (pinfunction "S_2") (pintype "passive"))
      (node (ref "JP13") (pin "6") (pinfunction "6_6") (pintype "passive"))
    )
    (net (code "43") (name "D25") (class "Default")
      (node (ref "JP1") (pin "6") (pinfunction "6_6") (pintype "passive"))
      (node (ref "JP13") (pin "5") (pinfunction "5_5") (pintype "passive"))
    )
    (net (code "44") (name "D26") (class "Default")
      (node (ref "JP13") (pin "8") (pinfunction "8_8") (pintype "passive"))
      (node (ref "JP6") (pin "15") (pinfunction "15_15") (pintype "passive"))
    )
    (net (code "45") (name "D27") (class "Default")
      (node (ref "JP1") (pin "7") (pinfunction "7_7") (pintype "passive"))
      (node (ref "JP13") (pin "7") (pinfunction "7_7") (pintype "passive"))
    )
    (net (code "46") (name "D28") (class "Default")
      (node (ref "JP13") (pin "10") (pinfunction "10_10") (pintype "passive"))
      (node (ref "JP6") (pin "14") (pinfunction "14_14") (pintype "passive"))
    )
    (net (code "47") (name "D29") (class "Default")
      (node (ref "JP1") (pin "8") (pinfunction "8_8") (pintype "passive"))
      (node (ref "JP13") (pin "9") (pinfunction "9_9") (pintype "passive"))
    )
    (net (code "48") (name "D30") (class "Default")
      (node (ref "JP13") (pin "12") (pinfunction "12_12") (pintype "passive"))
      (node (ref "JP6") (pin "13") (pinfunction "13_13") (pintype "passive"))
    )
    (net (code "49") (name "D31") (class "Default")
      (node (ref "JP13") (pin "11") (pinfunction "11_11") (pintype "passive"))
      (node (ref "JP8") (pin "3") (pinfunction "3_3") (pintype "passive"))
    )
    (net (code "50") (name "D32") (class "Default")
      (node (ref "JP13") (pin "14") (pinfunction "14_14") (pintype "passive"))
      (node (ref "JP6") (pin "12") (pinfunction "12_12") (pintype "passive"))
    )
    (net (code "51") (name "D33") (class "Default")
      (node (ref "JP13") (pin "13") (pinfunction "13_13") (pintype "passive"))
      (node (ref "JP8") (pin "5") (pinfunction "5_5") (pintype "passive"))
    )
    (net (code "52") (name "D34") (class "Default")
      (node (ref "JP13") (pin "16") (pinfunction "16_16") (pintype "passive"))
      (node (ref "JP6") (pin "11") (pinfunction "11_11") (pintype "passive"))
    )
    (net (code "53") (name "D35") (class "Default")
      (node (ref "JP1") (pin "2") (pinfunction "2_2") (pintype "passive"))
      (node (ref "JP13") (pin "15") (pinfunction "15_15") (pintype "passive"))
    )
    (net (code "54") (name "D36") (class "Default")
      (node (ref "JP13") (pin "18") (pinfunction "18_18") (pintype "passive"))
      (node (ref "JP6") (pin "9") (pinfunction "9_9") (pintype "passive"))
    )
    (net (code "55") (name "D37") (class "Default")
      (node (ref "JP1") (pin "1") (pinfunction "1_1") (pintype "passive"))
      (node (ref "JP13") (pin "17") (pinfunction "17_17") (pintype "passive"))
    )
    (net (code "56") (name "D38") (class "Default")
      (node (ref "JP13") (pin "20") (pinfunction "20_20") (pintype "passive"))
      (node (ref "JP6") (pin "7") (pinfunction "7_7") (pintype "passive"))
    )
    (net (code "57") (name "D39") (class "Default")
      (node (ref "JP13") (pin "19") (pinfunction "19_19") (pintype "passive"))
      (node (ref "JP6") (pin "10") (pinfunction "10_10") (pintype "passive"))
    )
    (net (code "58") (name "D40") (class "Default")
      (node (ref "JP13") (pin "22") (pinfunction "22_22") (pintype "passive"))
      (node (ref "JP6") (pin "8") (pinfunction "8_8") (pintype "passive"))
    )
    (net (code "59") (name "D41") (class "Default")
      (node (ref "JP13") (pin "21") (pinfunction "21_21") (pintype "passive"))
      (node (ref "JP8") (pin "8") (pinfunction "8_8") (pintype "passive"))
    )
    (net (code "60") (name "D42") (class "Default")
      (node (ref "JP13") (pin "24") (pinfunction "24_24") (pintype "passive"))
      (node (ref "JP6") (pin "5") (pinfunction "5_5") (pintype "passive"))
    )
    (net (code "61") (name "D43") (class "Default")
      (node (ref "JP13") (pin "23") (pinfunction "23_23") (pintype "passive"))
      (node (ref "JP6") (pin "6") (pinfunction "6_6") (pintype "passive"))
    )
    (net (code "62") (name "D44") (class "Default")
      (node (ref "JP13") (pin "26") (pinfunction "26_26") (pintype "passive"))
      (node (ref "JP6") (pin "3") (pinfunction "3_3") (pintype "passive"))
    )
    (net (code "63") (name "D45") (class "Default")
      (node (ref "JP13") (pin "25") (pinfunction "25_25") (pintype "passive"))
      (node (ref "JP6") (pin "4") (pinfunction "4_4") (pintype "passive"))
    )
    (net (code "64") (name "D49") (class "Default")
      (node (ref "JP13") (pin "29") (pinfunction "29_29") (pintype "passive"))
      (node (ref "JP8") (pin "7") (pinfunction "7_7") (pintype "passive"))
    )
    (net (code "65") (name "E0_STEP") (class "Default")
      (node (ref "JP3") (pin "6") (pinfunction "6_6") (pintype "passive"))
      (node (ref "JPE0") (pin "5") (pinfunction "5_5") (pintype "passive"))
    )
    (net (code "66") (name "E1_STEP") (class "Default")
      (node (ref "JP3") (pin "8") (pinfunction "8_8") (pintype "passive"))
      (node (ref "JPE1") (pin "5") (pinfunction "5_5") (pintype "passive"))
    )
    (net (code "67") (name "FLAG") (class "Default")
      (node (ref "JP13") (pin "27") (pinfunction "27_27") (pintype "passive"))
      (node (ref "JPE0") (pin "6") (pinfunction "6_6") (pintype "passive"))
      (node (ref "JPE1") (pin "6") (pinfunction "6_6") (pintype "passive"))
      (node (ref "JPX") (pin "6") (pinfunction "6_6") (pintype "passive"))
      (node (ref "JPY") (pin "6") (pinfunction "6_6") (pintype "passive"))
      (node (ref "JPZ") (pin "6") (pinfunction "6_6") (pintype "passive"))
    )
    (net (code "68") (name "GND") (class "Default")
      (node (ref "C3") (pin "-") (pinfunction "-_-") (pintype "passive"))
      (node (ref "C4") (pin "-") (pinfunction "-_-") (pintype "passive"))
      (node (ref "C5") (pin "-") (pinfunction "-_-") (pintype "passive"))
      (node (ref "C51") (pin "-") (pinfunction "-_-") (pintype "passive"))
      (node (ref "C6") (pin "2") (pinfunction "2_2") (pintype "passive"))
      (node (ref "D1") (pin "A") (pinfunction "A_A") (pintype "passive"))
      (node (ref "J1") (pin "1") (pinfunction "S_1") (pintype "passive"))
      (node (ref "J16") (pin "1") (pinfunction "S_1") (pintype "passive"))
      (node (ref "J17") (pin "1") (pinfunction "S_1") (pintype "passive"))
      (node (ref "J18") (pin "1") (pinfunction "S_1") (pintype "passive"))
      (node (ref "J19") (pin "1") (pinfunction "S_1") (pintype "passive"))
      (node (ref "J2") (pin "2") (pinfunction "S_2") (pintype "passive"))
      (node (ref "J20") (pin "3") (pinfunction "S_3") (pintype "passive"))
      (node (ref "J21") (pin "3") (pinfunction "S_3") (pintype "passive"))
      (node (ref "J22") (pin "3") (pinfunction "S_3") (pintype "passive"))
      (node (ref "J23") (pin "3") (pinfunction "S_3") (pintype "passive"))
      (node (ref "J24") (pin "3") (pinfunction "S_3") (pintype "passive"))
      (node (ref "J25") (pin "3") (pinfunction "S_3") (pintype "passive"))
      (node (ref "J3") (pin "2") (pinfunction "S_2") (pintype "passive"))
      (node (ref "J5") (pin "2") (pinfunction "S_2") (pintype "passive"))
      (node (ref "JP1") (pin "9") (pinfunction "9_9") (pintype "passive"))
      (node (ref "JP10") (pin "1") (pinfunction "1_1") (pintype "passive"))
      (node (ref "JP13") (pin "35") (pinfunction "35_35") (pintype "passive"))
      (node (ref "JP13") (pin "36") (pinfunction "36_36") (pintype "passive"))
      (node (ref "JP6") (pin "1") (pinfunction "1_1") (pintype "passive"))
      (node (ref "JP6") (pin "2") (pinfunction "2_2") (pintype "passive"))
      (node (ref "JP7") (pin "4") (pinfunction "4_4") (pintype "passive"))
      (node (ref "JP7") (pin "5") (pinfunction "5_5") (pintype "passive"))
      (node (ref "JP8") (pin "9") (pinfunction "9_9") (pintype "passive"))
      (node (ref "JP9") (pin "2") (pinfunction "2_2") (pintype "passive"))
      (node (ref "JPE0") (pin "1") (pinfunction "1_1") (pintype "passive"))
      (node (ref "JPE1") (pin "1") (pinfunction "1_1") (pintype "passive"))
      (node (ref "JPX") (pin "1") (pinfunction "1_1") (pintype "passive"))
      (node (ref "JPY") (pin "1") (pinfunction "1_1") (pintype "passive"))
      (node (ref "JPZ") (pin "1") (pinfunction "1_1") (pintype "passive"))
      (node (ref "LED1") (pin "C") (pinfunction "C_C") (pintype "passive"))
      (node (ref "OK1") (pin "2") (pinfunction "C_2") (pintype "passive"))
      (node (ref "OK1") (pin "4") (pinfunction "C_4") (pintype "passive"))
      (node (ref "OK1") (pin "6") (pinfunction "C_6") (pintype "passive"))
      (node (ref "OK2") (pin "2") (pinfunction "C_2") (pintype "passive"))
      (node (ref "OK2") (pin "4") (pinfunction "C_4") (pintype "passive"))
      (node (ref "OK2") (pin "6") (pinfunction "C_6") (pintype "passive"))
      (node (ref "OK2") (pin "8") (pinfunction "C_8") (pintype "passive"))
      (node (ref "Q3") (pin "S") (pinfunction "S_S") (pintype "passive"))
      (node (ref "Q4") (pin "S") (pinfunction "S_S") (pintype "passive"))
      (node (ref "Q5") (pin "S") (pinfunction "S_S") (pintype "passive"))
      (node (ref "R12") (pin "1") (pinfunction "1_1") (pintype "passive"))
      (node (ref "R14") (pin "1") (pinfunction "1_1") (pintype "passive"))
      (node (ref "R16") (pin "1") (pinfunction "1_1") (pintype "passive"))
      (node (ref "R24") (pin "1") (pinfunction "1_1") (pintype "passive"))
      (node (ref "R26") (pin "1") (pinfunction "1_1") (pintype "passive"))
      (node (ref "R28") (pin "1") (pinfunction "1_1") (pintype "passive"))
      (node (ref "R30") (pin "1") (pinfunction "1_1") (pintype "passive"))
      (node (ref "U$2") (pin "1") (pinfunction "S2_1") (pintype "passive"))
      (node (ref "U$2") (pin "3") (pinfunction "S1_3") (pintype "passive"))
      (node (ref "U$3") (pin "1") (pinfunction "S2_1") (pintype "passive"))
      (node (ref "U$3") (pin "3") (pinfunction "S1_3") (pintype "passive"))
      (node (ref "X1") (pin "2") (pinfunction "1_2") (pintype "passive"))
      (node (ref "X1") (pin "4") (pinfunction "1_4") (pintype "passive"))
    )
    (net (code "69") (name "MISO") (class "Default")
      (node (ref "JP13") (pin "32") (pinfunction "32_32") (pintype "passive"))
      (node (ref "JP8") (pin "1") (pinfunction "1_1") (pintype "passive"))
      (node (ref "JPE0") (pin "11") (pinfunction "11_11") (pintype "passive"))
      (node (ref "JPE1") (pin "11") (pinfunction "11_11") (pintype "passive"))
      (node (ref "JPX") (pin "11") (pinfunction "11_11") (pintype "passive"))
      (node (ref "JPY") (pin "11") (pinfunction "11_11") (pintype "passive"))
      (node (ref "JPZ") (pin "11") (pinfunction "11_11") (pintype "passive"))
    )
    (net (code "70") (name "MOSI") (class "Default")
      (node (ref "JP13") (pin "31") (pinfunction "31_31") (pintype "passive"))
      (node (ref "JP8") (pin "6") (pinfunction "6_6") (pintype "passive"))
      (node (ref "JPE0") (pin "9") (pinfunction "9_9") (pintype "passive"))
      (node (ref "JPE1") (pin "9") (pinfunction "9_9") (pintype "passive"))
      (node (ref "JPX") (pin "9") (pinfunction "9_9") (pintype "passive"))
      (node (ref "JPY") (pin "9") (pinfunction "9_9") (pintype "passive"))
      (node (ref "JPZ") (pin "9") (pinfunction "9_9") (pintype "passive"))
    )
    (net (code "71") (name "N.C") (class "Default")
      (node (ref "JP8") (pin "10") (pinfunction "10_10") (pintype "passive"))
    )
    (net (code "72") (name "Net-(C5-Pad+)") (class "Default")
      (node (ref "C5") (pin "+") (pinfunction "+_+") (pintype "passive"))
      (node (ref "C6") (pin "1") (pinfunction "1_1") (pintype "passive"))
      (node (ref "D1") (pin "C") (pinfunction "C_C") (pintype "passive"))
      (node (ref "D2") (pin "A") (pinfunction "A_A") (pintype "passive"))
      (node (ref "F2") (pin "P$3") (pinfunction "2_P$3") (pintype "passive"))
      (node (ref "F2") (pin "P$4") (pinfunction "2_P$4") (pintype "passive"))
      (node (ref "LED3") (pin "C") (pinfunction "C_C") (pintype "passive"))
    )
    (net (code "73") (name "Net-(F1-1-PadP$1)") (class "Default")
      (node (ref "F1") (pin "P$1") (pinfunction "1_P$1") (pintype "passive"))
      (node (ref "F1") (pin "P$2") (pinfunction "1_P$2") (pintype "passive"))
      (node (ref "R1") (pin "1") (pinfunction "1_1") (pintype "passive"))
      (node (ref "X1") (pin "1") (pinfunction "1_1") (pintype "passive"))
    )
    (net (code "74") (name "Net-(J12B-S)") (class "Default")
      (node (ref "J12") (pin "2") (pinfunction "S_2") (pintype "passive"))
      (node (ref "LED8") (pin "C") (pinfunction "C_C") (pintype "passive"))
      (node (ref "U$2") (pin "5") (pinfunction "D1_5") (pintype "passive"))
      (node (ref "U$2") (pin "6") (pinfunction "D1_6") (pintype "passive"))
    )
    (net (code "75") (name "Net-(J13B-S)") (class "Default")
      (node (ref "J13") (pin "2") (pinfunction "S_2") (pintype "passive"))
      (node (ref "LED9") (pin "C") (pinfunction "C_C") (pintype "passive"))
      (node (ref "U$2") (pin "7") (pinfunction "D2_7") (pintype "passive"))
      (node (ref "U$2") (pin "8") (pinfunction "D2_8") (pintype "passive"))
    )
    (net (code "76") (name "Net-(J14B-S)") (class "Default")
      (node (ref "J14") (pin "2") (pinfunction "S_2") (pintype "passive"))
      (node (ref "LED10") (pin "C") (pinfunction "C_C") (pintype "passive"))
      (node (ref "U$3") (pin "5") (pinfunction "D1_5") (pintype "passive"))
      (node (ref "U$3") (pin "6") (pinfunction "D1_6") (pintype "passive"))
    )
    (net (code "77") (name "Net-(J15B-S)") (class "Default")
      (node (ref "J15") (pin "2") (pinfunction "S_2") (pintype "passive"))
      (node (ref "LED11") (pin "C") (pinfunction "C_C") (pintype "passive"))
      (node (ref "U$3") (pin "7") (pinfunction "D2_7") (pintype "passive"))
      (node (ref "U$3") (pin "8") (pinfunction "D2_8") (pintype "passive"))
    )
    (net (code "78") (name "Net-(LED1-PadA)") (class "Default")
      (node (ref "LED1") (pin "A") (pinfunction "A_A") (pintype "passive"))
      (node (ref "R39") (pin "2") (pinfunction "2_2") (pintype "passive"))
    )
    (net (code "79") (name "Net-(LED2-PadA)") (class "Default")
      (node (ref "LED2") (pin "A") (pinfunction "A_A") (pintype "passive"))
      (node (ref "R1") (pin "2") (pinfunction "2_2") (pintype "passive"))
    )
    (net (code "80") (name "Net-(LED3-PadA)") (class "Default")
      (node (ref "LED3") (pin "A") (pinfunction "A_A") (pintype "passive"))
      (node (ref "R2") (pin "2") (pinfunction "2_2") (pintype "passive"))
    )
    (net (code "81") (name "Net-(LED4-PadA)") (class "Default")
      (node (ref "LED4") (pin "A") (pinfunction "A_A") (pintype "passive"))
      (node (ref "R31") (pin "1") (pinfunction "1_1") (pintype "passive"))
    )
    (net (code "82") (name "Net-(LED5-PadA)") (class "Default")
      (node (ref "LED5") (pin "A") (pinfunction "A_A") (pintype "passive"))
      (node (ref "R32") (pin "1") (pinfunction "1_1") (pintype "passive"))
    )
    (net (code "83") (name "Net-(LED6-PadA)") (class "Default")
      (node (ref "LED6") (pin "A") (pinfunction "A_A") (pintype "passive"))
      (node (ref "R33") (pin "1") (pinfunction "1_1") (pintype "passive"))
    )
    (net (code "84") (name "Net-(LED8-PadA)") (class "Default")
      (node (ref "LED8") (pin "A") (pinfunction "A_A") (pintype "passive"))
      (node (ref "R35") (pin "2") (pinfunction "2_2") (pintype "passive"))
    )
    (net (code "85") (name "Net-(LED9-PadA)") (class "Default")
      (node (ref "LED9") (pin "A") (pinfunction "A_A") (pintype "passive"))
      (node (ref "R36") (pin "2") (pinfunction "2_2") (pintype "passive"))
    )
    (net (code "86") (name "Net-(LED10-PadA)") (class "Default")
      (node (ref "LED10") (pin "A") (pinfunction "A_A") (pintype "passive"))
      (node (ref "R37") (pin "2") (pinfunction "2_2") (pintype "passive"))
    )
    (net (code "87") (name "Net-(LED11-PadA)") (class "Default")
      (node (ref "LED11") (pin "A") (pinfunction "A_A") (pintype "passive"))
      (node (ref "R38") (pin "2") (pinfunction "2_2") (pintype "passive"))
    )
    (net (code "88") (name "Net-(OK1A-A)") (class "Default")
      (node (ref "OK1") (pin "1") (pinfunction "A_1") (pintype "passive"))
      (node (ref "R7") (pin "2") (pinfunction "2_2") (pintype "passive"))
    )
    (net (code "89") (name "Net-(OK1A-COL)") (class "Default")
      (node (ref "OK1") (pin "16") (pinfunction "COL_16") (pintype "passive"))
      (node (ref "R11") (pin "1") (pinfunction "1_1") (pintype "passive"))
    )
    (net (code "90") (name "Net-(OK1B-A)") (class "Default")
      (node (ref "OK1") (pin "3") (pinfunction "A_3") (pintype "passive"))
      (node (ref "R8") (pin "2") (pinfunction "2_2") (pintype "passive"))
    )
    (net (code "91") (name "Net-(OK1B-COL)") (class "Default")
      (node (ref "OK1") (pin "14") (pinfunction "COL_14") (pintype "passive"))
      (node (ref "R13") (pin "1") (pinfunction "1_1") (pintype "passive"))
    )
    (net (code "92") (name "Net-(OK1C-A)") (class "Default")
      (node (ref "OK1") (pin "5") (pinfunction "A_5") (pintype "passive"))
      (node (ref "R9") (pin "2") (pinfunction "2_2") (pintype "passive"))
    )
    (net (code "93") (name "Net-(OK1C-COL)") (class "Default")
      (node (ref "OK1") (pin "12") (pinfunction "COL_12") (pintype "passive"))
      (node (ref "R15") (pin "1") (pinfunction "1_1") (pintype "passive"))
    )
    (net (code "94") (name "Net-(OK2A-A)") (class "Default")
      (node (ref "OK2") (pin "1") (pinfunction "A_1") (pintype "passive"))
      (node (ref "R19") (pin "2") (pinfunction "2_2") (pintype "passive"))
    )
    (net (code "95") (name "Net-(OK2A-COL)") (class "Default")
      (node (ref "OK2") (pin "16") (pinfunction "COL_16") (pintype "passive"))
      (node (ref "R23") (pin "1") (pinfunction "1_1") (pintype "passive"))
    )
    (net (code "96") (name "Net-(OK2B-A)") (class "Default")
      (node (ref "OK2") (pin "3") (pinfunction "A_3") (pintype "passive"))
      (node (ref "R20") (pin "2") (pinfunction "2_2") (pintype "passive"))
    )
    (net (code "97") (name "Net-(OK2B-COL)") (class "Default")
      (node (ref "OK2") (pin "14") (pinfunction "COL_14") (pintype "passive"))
      (node (ref "R25") (pin "1") (pinfunction "1_1") (pintype "passive"))
    )
    (net (code "98") (name "Net-(OK2C-A)") (class "Default")
      (node (ref "OK2") (pin "5") (pinfunction "A_5") (pintype "passive"))
      (node (ref "R21") (pin "2") (pinfunction "2_2") (pintype "passive"))
    )
    (net (code "99") (name "Net-(OK2C-COL)") (class "Default")
      (node (ref "OK2") (pin "12") (pinfunction "COL_12") (pintype "passive"))
      (node (ref "R27") (pin "1") (pinfunction "1_1") (pintype "passive"))
    )
    (net (code "100") (name "Net-(OK2D-A)") (class "Default")
      (node (ref "OK2") (pin "7") (pinfunction "A_7") (pintype "passive"))
      (node (ref "R22") (pin "2") (pinfunction "2_2") (pintype "passive"))
    )
    (net (code "101") (name "Net-(OK2D-COL)") (class "Default")
      (node (ref "OK2") (pin "10") (pinfunction "COL_10") (pintype "passive"))
      (node (ref "R29") (pin "1") (pinfunction "1_1") (pintype "passive"))
    )
    (net (code "102") (name "Net-(X1C-1)") (class "Default")
      (node (ref "F2") (pin "P$1") (pinfunction "1_P$1") (pintype "passive"))
      (node (ref "F2") (pin "P$2") (pinfunction "1_P$2") (pintype "passive"))
      (node (ref "R2") (pin "1") (pinfunction "1_1") (pintype "passive"))
      (node (ref "X1") (pin "3") (pinfunction "1_3") (pintype "passive"))
    )
    (net (code "103") (name "Net-(X2B-1)") (class "Default")
      (node (ref "LED4") (pin "C") (pinfunction "C_C") (pintype "passive"))
      (node (ref "Q3") (pin "D") (pinfunction "D_D") (pintype "passive"))
      (node (ref "X2") (pin "2") (pinfunction "1_2") (pintype "passive"))
    )
    (net (code "104") (name "Net-(X3B-1)") (class "Default")
      (node (ref "LED5") (pin "C") (pinfunction "C_C") (pintype "passive"))
      (node (ref "Q4") (pin "D") (pinfunction "D_D") (pintype "passive"))
      (node (ref "X3") (pin "2") (pinfunction "1_2") (pintype "passive"))
    )
    (net (code "105") (name "Net-(X4B-1)") (class "Default")
      (node (ref "LED6") (pin "C") (pinfunction "C_C") (pintype "passive"))
      (node (ref "Q5") (pin "D") (pinfunction "D_D") (pintype "passive"))
      (node (ref "X4") (pin "2") (pinfunction "1_2") (pintype "passive"))
    )
    (net (code "106") (name "RESET") (class "Default")
      (node (ref "JP13") (pin "28") (pinfunction "28_28") (pintype "passive"))
      (node (ref "JPE0") (pin "4") (pinfunction "4_4") (pintype "passive"))
      (node (ref "JPE1") (pin "4") (pinfunction "4_4") (pintype "passive"))
      (node (ref "JPX") (pin "4") (pinfunction "4_4") (pintype "passive"))
      (node (ref "JPY") (pin "4") (pinfunction "4_4") (pintype "passive"))
      (node (ref "JPZ") (pin "4") (pinfunction "4_4") (pintype "passive"))
    )
    (net (code "107") (name "RESET_1") (class "Default")
      (node (ref "J1") (pin "2") (pinfunction "S_2") (pintype "passive"))
      (node (ref "JP7") (pin "1") (pinfunction "1_1") (pintype "passive"))
    )
    (net (code "108") (name "SCK") (class "Default")
      (node (ref "JP13") (pin "34") (pinfunction "34_34") (pintype "passive"))
      (node (ref "JP8") (pin "2") (pinfunction "2_2") (pintype "passive"))
      (node (ref "JPE0") (pin "10") (pinfunction "10_10") (pintype "passive"))
      (node (ref "JPE1") (pin "10") (pinfunction "10_10") (pintype "passive"))
      (node (ref "JPX") (pin "10") (pinfunction "10_10") (pintype "passive"))
      (node (ref "JPY") (pin "10") (pinfunction "10_10") (pintype "passive"))
      (node (ref "JPZ") (pin "10") (pinfunction "10_10") (pintype "passive"))
    )
    (net (code "109") (name "V_GS1") (class "Default")
      (node (ref "OK1") (pin "15") (pinfunction "EMIT_15") (pintype "passive"))
      (node (ref "Q5") (pin "G") (pinfunction "G_G") (pintype "passive"))
      (node (ref "R12") (pin "2") (pinfunction "2_2") (pintype "passive"))
    )
    (net (code "110") (name "V_GS2") (class "Default")
      (node (ref "OK1") (pin "13") (pinfunction "EMIT_13") (pintype "passive"))
      (node (ref "Q4") (pin "G") (pinfunction "G_G") (pintype "passive"))
      (node (ref "R14") (pin "2") (pinfunction "2_2") (pintype "passive"))
    )
    (net (code "111") (name "V_GS3") (class "Default")
      (node (ref "OK1") (pin "11") (pinfunction "EMIT_11") (pintype "passive"))
      (node (ref "Q3") (pin "G") (pinfunction "G_G") (pintype "passive"))
      (node (ref "R16") (pin "2") (pinfunction "2_2") (pintype "passive"))
    )
    (net (code "112") (name "V_GS_FAN1") (class "Default")
      (node (ref "OK2") (pin "11") (pinfunction "EMIT_11") (pintype "passive"))
      (node (ref "R28") (pin "2") (pinfunction "2_2") (pintype "passive"))
      (node (ref "U$2") (pin "4") (pinfunction "G1_4") (pintype "passive"))
    )
    (net (code "113") (name "V_GS_FAN2") (class "Default")
      (node (ref "OK2") (pin "9") (pinfunction "EMIT_9") (pintype "passive"))
      (node (ref "R30") (pin "2") (pinfunction "2_2") (pintype "passive"))
      (node (ref "U$2") (pin "2") (pinfunction "G2_2") (pintype "passive"))
    )
    (net (code "114") (name "V_GS_FAN3") (class "Default")
      (node (ref "OK2") (pin "15") (pinfunction "EMIT_15") (pintype "passive"))
      (node (ref "R24") (pin "2") (pinfunction "2_2") (pintype "passive"))
      (node (ref "U$3") (pin "4") (pinfunction "G1_4") (pintype "passive"))
    )
    (net (code "115") (name "V_GS_FAN4") (class "Default")
      (node (ref "OK2") (pin "13") (pinfunction "EMIT_13") (pintype "passive"))
      (node (ref "R26") (pin "2") (pinfunction "2_2") (pintype "passive"))
      (node (ref "U$3") (pin "2") (pinfunction "G2_2") (pintype "passive"))
    )
    (net (code "116") (name "V_IN") (class "Default")
      (node (ref "D2") (pin "C") (pinfunction "C_C") (pintype "passive"))
      (node (ref "JP7") (pin "6") (pinfunction "6_6") (pintype "passive"))
      (node (ref "R11") (pin "2") (pinfunction "2_2") (pintype "passive"))
      (node (ref "R13") (pin "2") (pinfunction "2_2") (pintype "passive"))
      (node (ref "R15") (pin "2") (pinfunction "2_2") (pintype "passive"))
      (node (ref "R23") (pin "2") (pinfunction "2_2") (pintype "passive"))
      (node (ref "R25") (pin "2") (pinfunction "2_2") (pintype "passive"))
      (node (ref "R27") (pin "2") (pinfunction "2_2") (pintype "passive"))
      (node (ref "R29") (pin "2") (pinfunction "2_2") (pintype "passive"))
    )
    (net (code "117") (name "X_STEP") (class "Default")
      (node (ref "JP2") (pin "4") (pinfunction "4_4") (pintype "passive"))
      (node (ref "JPX") (pin "5") (pinfunction "5_5") (pintype "passive"))
    )
    (net (code "118") (name "Y_STEP") (class "Default")
      (node (ref "JP2") (pin "6") (pinfunction "6_6") (pintype "passive"))
      (node (ref "JPY") (pin "5") (pinfunction "5_5") (pintype "passive"))
    )
    (net (code "119") (name "Z_STEP") (class "Default")
      (node (ref "JP3") (pin "3") (pinfunction "3_3") (pintype "passive"))
      (node (ref "JPZ") (pin "5") (pinfunction "5_5") (pintype "passive"))
    )
    (net (code "120") (name "unconnected-(OK1D-A-Pad7)") (class "Default")
      (node (ref "OK1") (pin "7") (pinfunction "A_7") (pintype "passive"))
    )
    (net (code "121") (name "unconnected-(OK1D-C-Pad8)") (class "Default")
      (node (ref "OK1") (pin "8") (pinfunction "C_8") (pintype "passive"))
    )
    (net (code "122") (name "unconnected-(OK1D-COL-Pad10)") (class "Default")
      (node (ref "OK1") (pin "10") (pinfunction "COL_10") (pintype "passive"))
    )
    (net (code "123") (name "unconnected-(OK1D-EMIT-Pad9)") (class "Default")
      (node (ref "OK1") (pin "9") (pinfunction "EMIT_9") (pintype "passive"))
    )
  )
)
